# Projeto_PD_2021-02-18_15-49-25.net
KiCad netlist of a schematic drawn in EasyEDA
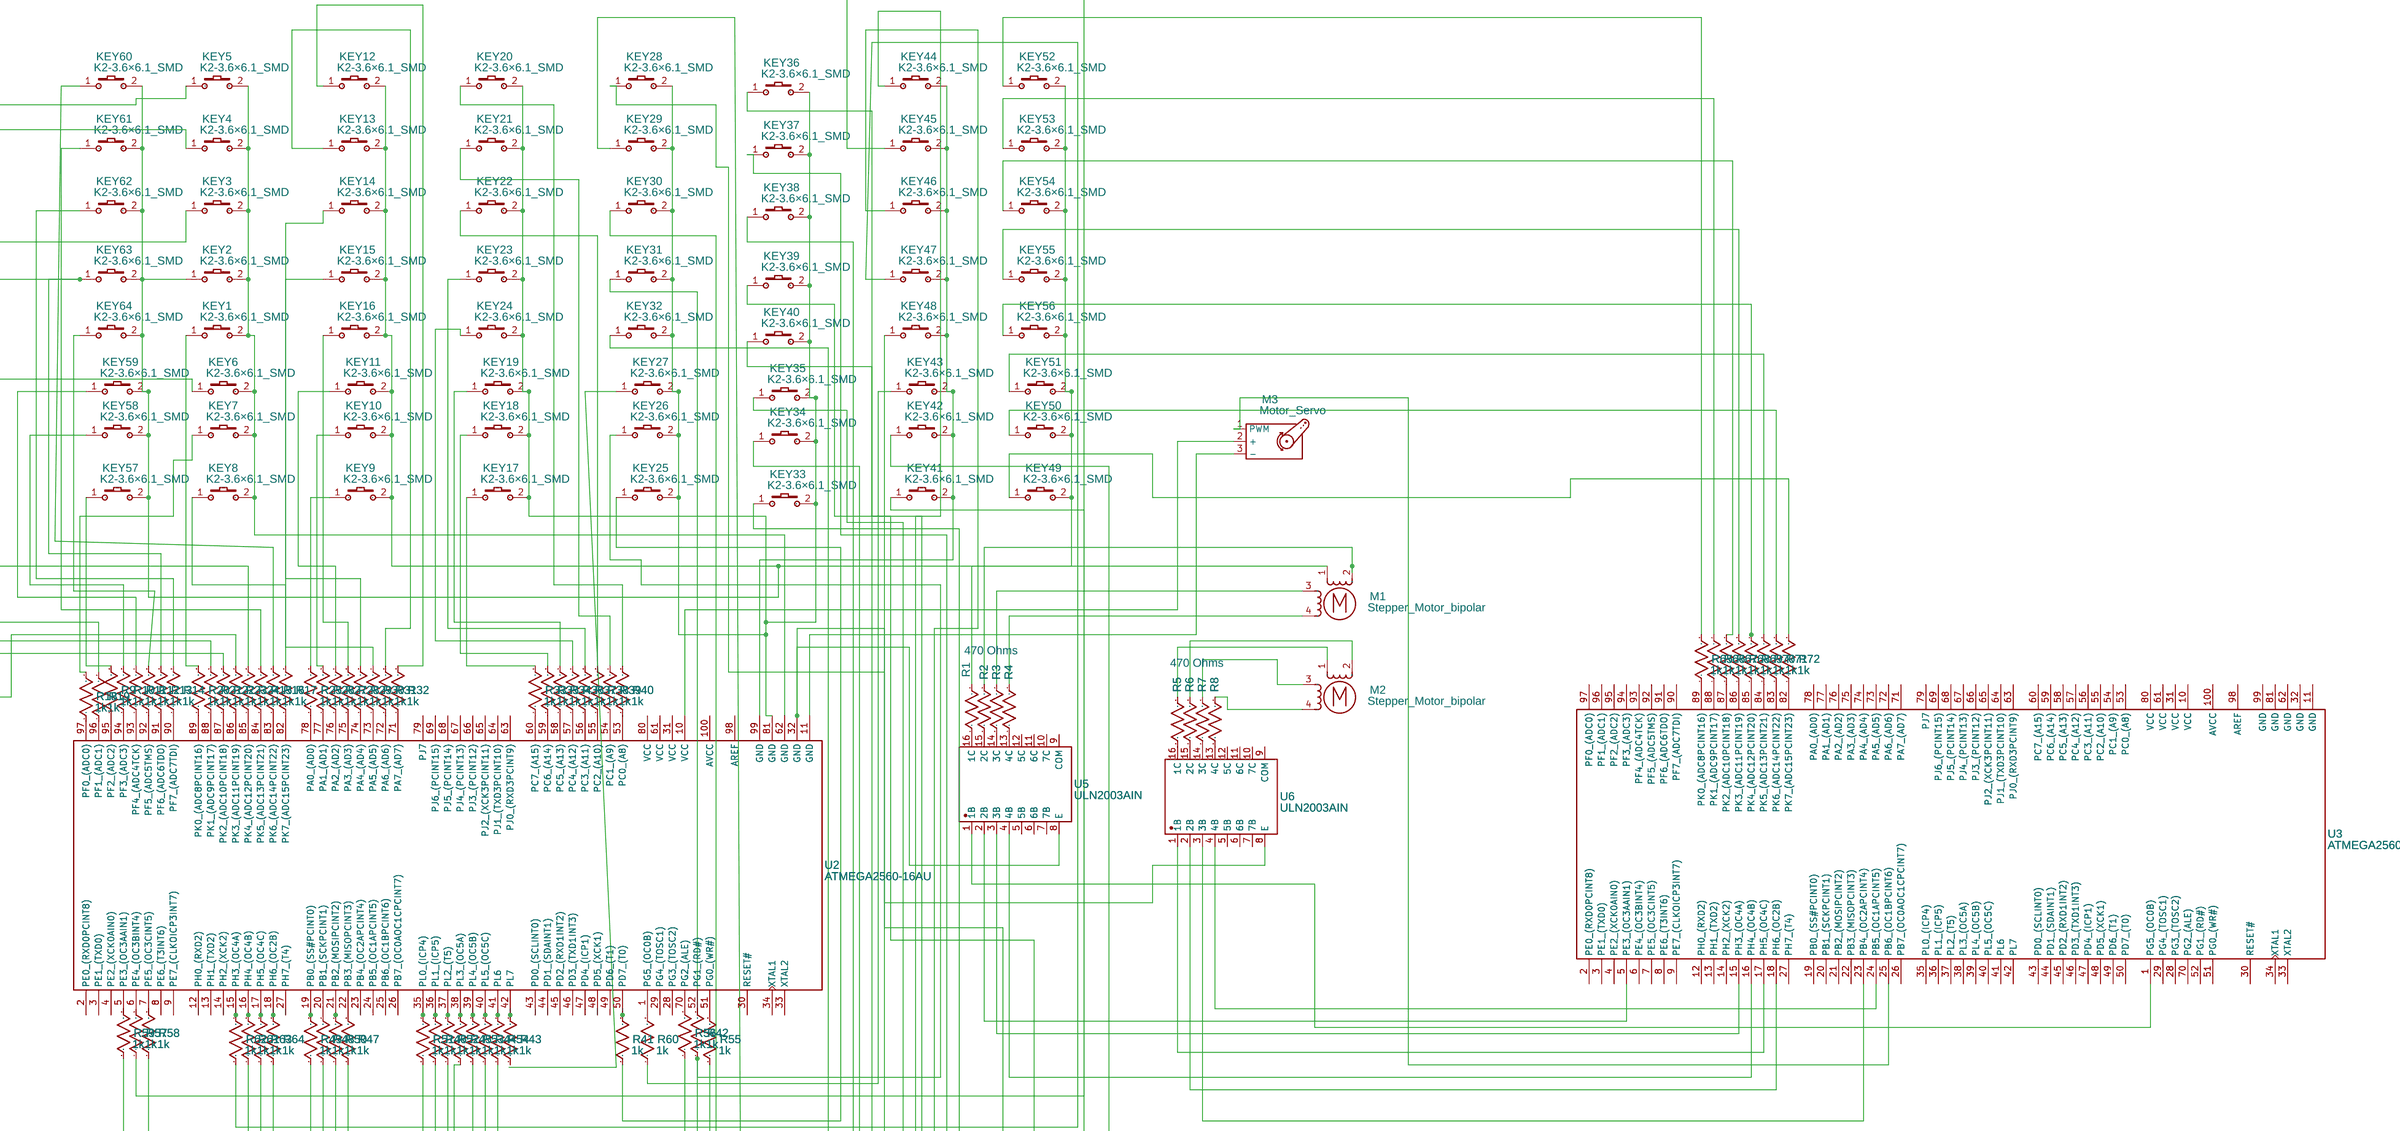
[diagram p0: schematic sheet]

(export (version "E")
  (design (tool "Eeschema 10.0.6"))
  (components
    (comp (ref "KEY1")
      (value "K2-3.6×6.1_SMD")
      (fields
        (field (name "BOM_Manufacturer Part") "K2-1107ST-A4SW-06")
        (field (name "BOM_Supplier Part") "C118141")
      )
      (libsource (lib "") (part "K2-3.6×6.1_SMD"))
    )
    (comp (ref "KEY2")
      (value "K2-3.6×6.1_SMD")
      (fields
        (field (name "BOM_Manufacturer Part") "K2-1107ST-A4SW-06")
        (field (name "BOM_Supplier Part") "C118141")
      )
      (libsource (lib "") (part "K2-3.6×6.1_SMD"))
    )
    (comp (ref "KEY3")
      (value "K2-3.6×6.1_SMD")
      (fields
        (field (name "BOM_Manufacturer Part") "K2-1107ST-A4SW-06")
        (field (name "BOM_Supplier Part") "C118141")
      )
      (libsource (lib "") (part "K2-3.6×6.1_SMD"))
    )
    (comp (ref "KEY4")
      (value "K2-3.6×6.1_SMD")
      (fields
        (field (name "BOM_Manufacturer Part") "K2-1107ST-A4SW-06")
        (field (name "BOM_Supplier Part") "C118141")
      )
      (libsource (lib "") (part "K2-3.6×6.1_SMD"))
    )
    (comp (ref "KEY5")
      (value "K2-3.6×6.1_SMD")
      (fields
        (field (name "BOM_Manufacturer Part") "K2-1107ST-A4SW-06")
        (field (name "BOM_Supplier Part") "C118141")
      )
      (libsource (lib "") (part "K2-3.6×6.1_SMD"))
    )
    (comp (ref "KEY6")
      (value "K2-3.6×6.1_SMD")
      (fields
        (field (name "BOM_Manufacturer Part") "K2-1107ST-A4SW-06")
        (field (name "BOM_Supplier Part") "C118141")
      )
      (libsource (lib "") (part "K2-3.6×6.1_SMD"))
    )
    (comp (ref "KEY7")
      (value "K2-3.6×6.1_SMD")
      (fields
        (field (name "BOM_Manufacturer Part") "K2-1107ST-A4SW-06")
        (field (name "BOM_Supplier Part") "C118141")
      )
      (libsource (lib "") (part "K2-3.6×6.1_SMD"))
    )
    (comp (ref "KEY8")
      (value "K2-3.6×6.1_SMD")
      (fields
        (field (name "BOM_Manufacturer Part") "K2-1107ST-A4SW-06")
        (field (name "BOM_Supplier Part") "C118141")
      )
      (libsource (lib "") (part "K2-3.6×6.1_SMD"))
    )
    (comp (ref "KEY9")
      (value "K2-3.6×6.1_SMD")
      (fields
        (field (name "BOM_Manufacturer Part") "K2-1107ST-A4SW-06")
        (field (name "BOM_Supplier Part") "C118141")
      )
      (libsource (lib "") (part "K2-3.6×6.1_SMD"))
    )
    (comp (ref "KEY10")
      (value "K2-3.6×6.1_SMD")
      (fields
        (field (name "BOM_Manufacturer Part") "K2-1107ST-A4SW-06")
        (field (name "BOM_Supplier Part") "C118141")
      )
      (libsource (lib "") (part "K2-3.6×6.1_SMD"))
    )
    (comp (ref "KEY11")
      (value "K2-3.6×6.1_SMD")
      (fields
        (field (name "BOM_Manufacturer Part") "K2-1107ST-A4SW-06")
        (field (name "BOM_Supplier Part") "C118141")
      )
      (libsource (lib "") (part "K2-3.6×6.1_SMD"))
    )
    (comp (ref "KEY12")
      (value "K2-3.6×6.1_SMD")
      (fields
        (field (name "BOM_Manufacturer Part") "K2-1107ST-A4SW-06")
        (field (name "BOM_Supplier Part") "C118141")
      )
      (libsource (lib "") (part "K2-3.6×6.1_SMD"))
    )
    (comp (ref "KEY13")
      (value "K2-3.6×6.1_SMD")
      (fields
        (field (name "BOM_Manufacturer Part") "K2-1107ST-A4SW-06")
        (field (name "BOM_Supplier Part") "C118141")
      )
      (libsource (lib "") (part "K2-3.6×6.1_SMD"))
    )
    (comp (ref "KEY14")
      (value "K2-3.6×6.1_SMD")
      (fields
        (field (name "BOM_Manufacturer Part") "K2-1107ST-A4SW-06")
        (field (name "BOM_Supplier Part") "C118141")
      )
      (libsource (lib "") (part "K2-3.6×6.1_SMD"))
    )
    (comp (ref "KEY15")
      (value "K2-3.6×6.1_SMD")
      (fields
        (field (name "BOM_Manufacturer Part") "K2-1107ST-A4SW-06")
        (field (name "BOM_Supplier Part") "C118141")
      )
      (libsource (lib "") (part "K2-3.6×6.1_SMD"))
    )
    (comp (ref "KEY16")
      (value "K2-3.6×6.1_SMD")
      (fields
        (field (name "BOM_Manufacturer Part") "K2-1107ST-A4SW-06")
        (field (name "BOM_Supplier Part") "C118141")
      )
      (libsource (lib "") (part "K2-3.6×6.1_SMD"))
    )
    (comp (ref "KEY17")
      (value "K2-3.6×6.1_SMD")
      (fields
        (field (name "BOM_Manufacturer Part") "K2-1107ST-A4SW-06")
        (field (name "BOM_Supplier Part") "C118141")
      )
      (libsource (lib "") (part "K2-3.6×6.1_SMD"))
    )
    (comp (ref "KEY18")
      (value "K2-3.6×6.1_SMD")
      (fields
        (field (name "BOM_Manufacturer Part") "K2-1107ST-A4SW-06")
        (field (name "BOM_Supplier Part") "C118141")
      )
      (libsource (lib "") (part "K2-3.6×6.1_SMD"))
    )
    (comp (ref "KEY19")
      (value "K2-3.6×6.1_SMD")
      (fields
        (field (name "BOM_Manufacturer Part") "K2-1107ST-A4SW-06")
        (field (name "BOM_Supplier Part") "C118141")
      )
      (libsource (lib "") (part "K2-3.6×6.1_SMD"))
    )
    (comp (ref "KEY20")
      (value "K2-3.6×6.1_SMD")
      (fields
        (field (name "BOM_Manufacturer Part") "K2-1107ST-A4SW-06")
        (field (name "BOM_Supplier Part") "C118141")
      )
      (libsource (lib "") (part "K2-3.6×6.1_SMD"))
    )
    (comp (ref "KEY21")
      (value "K2-3.6×6.1_SMD")
      (fields
        (field (name "BOM_Manufacturer Part") "K2-1107ST-A4SW-06")
        (field (name "BOM_Supplier Part") "C118141")
      )
      (libsource (lib "") (part "K2-3.6×6.1_SMD"))
    )
    (comp (ref "KEY22")
      (value "K2-3.6×6.1_SMD")
      (fields
        (field (name "BOM_Manufacturer Part") "K2-1107ST-A4SW-06")
        (field (name "BOM_Supplier Part") "C118141")
      )
      (libsource (lib "") (part "K2-3.6×6.1_SMD"))
    )
    (comp (ref "KEY23")
      (value "K2-3.6×6.1_SMD")
      (fields
        (field (name "BOM_Manufacturer Part") "K2-1107ST-A4SW-06")
        (field (name "BOM_Supplier Part") "C118141")
      )
      (libsource (lib "") (part "K2-3.6×6.1_SMD"))
    )
    (comp (ref "KEY24")
      (value "K2-3.6×6.1_SMD")
      (fields
        (field (name "BOM_Manufacturer Part") "K2-1107ST-A4SW-06")
        (field (name "BOM_Supplier Part") "C118141")
      )
      (libsource (lib "") (part "K2-3.6×6.1_SMD"))
    )
    (comp (ref "KEY25")
      (value "K2-3.6×6.1_SMD")
      (fields
        (field (name "BOM_Manufacturer Part") "K2-1107ST-A4SW-06")
        (field (name "BOM_Supplier Part") "C118141")
      )
      (libsource (lib "") (part "K2-3.6×6.1_SMD"))
    )
    (comp (ref "KEY26")
      (value "K2-3.6×6.1_SMD")
      (fields
        (field (name "BOM_Manufacturer Part") "K2-1107ST-A4SW-06")
        (field (name "BOM_Supplier Part") "C118141")
      )
      (libsource (lib "") (part "K2-3.6×6.1_SMD"))
    )
    (comp (ref "KEY27")
      (value "K2-3.6×6.1_SMD")
      (fields
        (field (name "BOM_Manufacturer Part") "K2-1107ST-A4SW-06")
        (field (name "BOM_Supplier Part") "C118141")
      )
      (libsource (lib "") (part "K2-3.6×6.1_SMD"))
    )
    (comp (ref "KEY28")
      (value "K2-3.6×6.1_SMD")
      (fields
        (field (name "BOM_Manufacturer Part") "K2-1107ST-A4SW-06")
        (field (name "BOM_Supplier Part") "C118141")
      )
      (libsource (lib "") (part "K2-3.6×6.1_SMD"))
    )
    (comp (ref "KEY29")
      (value "K2-3.6×6.1_SMD")
      (fields
        (field (name "BOM_Manufacturer Part") "K2-1107ST-A4SW-06")
        (field (name "BOM_Supplier Part") "C118141")
      )
      (libsource (lib "") (part "K2-3.6×6.1_SMD"))
    )
    (comp (ref "KEY30")
      (value "K2-3.6×6.1_SMD")
      (fields
        (field (name "BOM_Manufacturer Part") "K2-1107ST-A4SW-06")
        (field (name "BOM_Supplier Part") "C118141")
      )
      (libsource (lib "") (part "K2-3.6×6.1_SMD"))
    )
    (comp (ref "KEY31")
      (value "K2-3.6×6.1_SMD")
      (fields
        (field (name "BOM_Manufacturer Part") "K2-1107ST-A4SW-06")
        (field (name "BOM_Supplier Part") "C118141")
      )
      (libsource (lib "") (part "K2-3.6×6.1_SMD"))
    )
    (comp (ref "KEY32")
      (value "K2-3.6×6.1_SMD")
      (fields
        (field (name "BOM_Manufacturer Part") "K2-1107ST-A4SW-06")
        (field (name "BOM_Supplier Part") "C118141")
      )
      (libsource (lib "") (part "K2-3.6×6.1_SMD"))
    )
    (comp (ref "KEY33")
      (value "K2-3.6×6.1_SMD")
      (fields
        (field (name "BOM_Manufacturer Part") "K2-1107ST-A4SW-06")
        (field (name "BOM_Supplier Part") "C118141")
      )
      (libsource (lib "") (part "K2-3.6×6.1_SMD"))
    )
    (comp (ref "KEY34")
      (value "K2-3.6×6.1_SMD")
      (fields
        (field (name "BOM_Manufacturer Part") "K2-1107ST-A4SW-06")
        (field (name "BOM_Supplier Part") "C118141")
      )
      (libsource (lib "") (part "K2-3.6×6.1_SMD"))
    )
    (comp (ref "KEY35")
      (value "K2-3.6×6.1_SMD")
      (fields
        (field (name "BOM_Manufacturer Part") "K2-1107ST-A4SW-06")
        (field (name "BOM_Supplier Part") "C118141")
      )
      (libsource (lib "") (part "K2-3.6×6.1_SMD"))
    )
    (comp (ref "KEY36")
      (value "K2-3.6×6.1_SMD")
      (fields
        (field (name "BOM_Manufacturer Part") "K2-1107ST-A4SW-06")
        (field (name "BOM_Supplier Part") "C118141")
      )
      (libsource (lib "") (part "K2-3.6×6.1_SMD"))
    )
    (comp (ref "KEY37")
      (value "K2-3.6×6.1_SMD")
      (fields
        (field (name "BOM_Manufacturer Part") "K2-1107ST-A4SW-06")
        (field (name "BOM_Supplier Part") "C118141")
      )
      (libsource (lib "") (part "K2-3.6×6.1_SMD"))
    )
    (comp (ref "KEY38")
      (value "K2-3.6×6.1_SMD")
      (fields
        (field (name "BOM_Manufacturer Part") "K2-1107ST-A4SW-06")
        (field (name "BOM_Supplier Part") "C118141")
      )
      (libsource (lib "") (part "K2-3.6×6.1_SMD"))
    )
    (comp (ref "KEY39")
      (value "K2-3.6×6.1_SMD")
      (fields
        (field (name "BOM_Manufacturer Part") "K2-1107ST-A4SW-06")
        (field (name "BOM_Supplier Part") "C118141")
      )
      (libsource (lib "") (part "K2-3.6×6.1_SMD"))
    )
    (comp (ref "KEY40")
      (value "K2-3.6×6.1_SMD")
      (fields
        (field (name "BOM_Manufacturer Part") "K2-1107ST-A4SW-06")
        (field (name "BOM_Supplier Part") "C118141")
      )
      (libsource (lib "") (part "K2-3.6×6.1_SMD"))
    )
    (comp (ref "KEY41")
      (value "K2-3.6×6.1_SMD")
      (fields
        (field (name "BOM_Manufacturer Part") "K2-1107ST-A4SW-06")
        (field (name "BOM_Supplier Part") "C118141")
      )
      (libsource (lib "") (part "K2-3.6×6.1_SMD"))
    )
    (comp (ref "KEY42")
      (value "K2-3.6×6.1_SMD")
      (fields
        (field (name "BOM_Manufacturer Part") "K2-1107ST-A4SW-06")
        (field (name "BOM_Supplier Part") "C118141")
      )
      (libsource (lib "") (part "K2-3.6×6.1_SMD"))
    )
    (comp (ref "KEY43")
      (value "K2-3.6×6.1_SMD")
      (fields
        (field (name "BOM_Manufacturer Part") "K2-1107ST-A4SW-06")
        (field (name "BOM_Supplier Part") "C118141")
      )
      (libsource (lib "") (part "K2-3.6×6.1_SMD"))
    )
    (comp (ref "KEY44")
      (value "K2-3.6×6.1_SMD")
      (fields
        (field (name "BOM_Manufacturer Part") "K2-1107ST-A4SW-06")
        (field (name "BOM_Supplier Part") "C118141")
      )
      (libsource (lib "") (part "K2-3.6×6.1_SMD"))
    )
    (comp (ref "KEY45")
      (value "K2-3.6×6.1_SMD")
      (fields
        (field (name "BOM_Manufacturer Part") "K2-1107ST-A4SW-06")
        (field (name "BOM_Supplier Part") "C118141")
      )
      (libsource (lib "") (part "K2-3.6×6.1_SMD"))
    )
    (comp (ref "KEY46")
      (value "K2-3.6×6.1_SMD")
      (fields
        (field (name "BOM_Manufacturer Part") "K2-1107ST-A4SW-06")
        (field (name "BOM_Supplier Part") "C118141")
      )
      (libsource (lib "") (part "K2-3.6×6.1_SMD"))
    )
    (comp (ref "KEY47")
      (value "K2-3.6×6.1_SMD")
      (fields
        (field (name "BOM_Manufacturer Part") "K2-1107ST-A4SW-06")
        (field (name "BOM_Supplier Part") "C118141")
      )
      (libsource (lib "") (part "K2-3.6×6.1_SMD"))
    )
    (comp (ref "KEY48")
      (value "K2-3.6×6.1_SMD")
      (fields
        (field (name "BOM_Manufacturer Part") "K2-1107ST-A4SW-06")
        (field (name "BOM_Supplier Part") "C118141")
      )
      (libsource (lib "") (part "K2-3.6×6.1_SMD"))
    )
    (comp (ref "KEY49")
      (value "K2-3.6×6.1_SMD")
      (fields
        (field (name "BOM_Manufacturer Part") "K2-1107ST-A4SW-06")
        (field (name "BOM_Supplier Part") "C118141")
      )
      (libsource (lib "") (part "K2-3.6×6.1_SMD"))
    )
    (comp (ref "KEY50")
      (value "K2-3.6×6.1_SMD")
      (fields
        (field (name "BOM_Manufacturer Part") "K2-1107ST-A4SW-06")
        (field (name "BOM_Supplier Part") "C118141")
      )
      (libsource (lib "") (part "K2-3.6×6.1_SMD"))
    )
    (comp (ref "KEY51")
      (value "K2-3.6×6.1_SMD")
      (fields
        (field (name "BOM_Manufacturer Part") "K2-1107ST-A4SW-06")
        (field (name "BOM_Supplier Part") "C118141")
      )
      (libsource (lib "") (part "K2-3.6×6.1_SMD"))
    )
    (comp (ref "KEY52")
      (value "K2-3.6×6.1_SMD")
      (fields
        (field (name "BOM_Manufacturer Part") "K2-1107ST-A4SW-06")
        (field (name "BOM_Supplier Part") "C118141")
      )
      (libsource (lib "") (part "K2-3.6×6.1_SMD"))
    )
    (comp (ref "KEY53")
      (value "K2-3.6×6.1_SMD")
      (fields
        (field (name "BOM_Manufacturer Part") "K2-1107ST-A4SW-06")
        (field (name "BOM_Supplier Part") "C118141")
      )
      (libsource (lib "") (part "K2-3.6×6.1_SMD"))
    )
    (comp (ref "KEY54")
      (value "K2-3.6×6.1_SMD")
      (fields
        (field (name "BOM_Manufacturer Part") "K2-1107ST-A4SW-06")
        (field (name "BOM_Supplier Part") "C118141")
      )
      (libsource (lib "") (part "K2-3.6×6.1_SMD"))
    )
    (comp (ref "KEY55")
      (value "K2-3.6×6.1_SMD")
      (fields
        (field (name "BOM_Manufacturer Part") "K2-1107ST-A4SW-06")
        (field (name "BOM_Supplier Part") "C118141")
      )
      (libsource (lib "") (part "K2-3.6×6.1_SMD"))
    )
    (comp (ref "KEY56")
      (value "K2-3.6×6.1_SMD")
      (fields
        (field (name "BOM_Manufacturer Part") "K2-1107ST-A4SW-06")
        (field (name "BOM_Supplier Part") "C118141")
      )
      (libsource (lib "") (part "K2-3.6×6.1_SMD"))
    )
    (comp (ref "KEY57")
      (value "K2-3.6×6.1_SMD")
      (fields
        (field (name "BOM_Manufacturer Part") "K2-1107ST-A4SW-06")
        (field (name "BOM_Supplier Part") "C118141")
      )
      (libsource (lib "") (part "K2-3.6×6.1_SMD"))
    )
    (comp (ref "KEY58")
      (value "K2-3.6×6.1_SMD")
      (fields
        (field (name "BOM_Manufacturer Part") "K2-1107ST-A4SW-06")
        (field (name "BOM_Supplier Part") "C118141")
      )
      (libsource (lib "") (part "K2-3.6×6.1_SMD"))
    )
    (comp (ref "KEY59")
      (value "K2-3.6×6.1_SMD")
      (fields
        (field (name "BOM_Manufacturer Part") "K2-1107ST-A4SW-06")
        (field (name "BOM_Supplier Part") "C118141")
      )
      (libsource (lib "") (part "K2-3.6×6.1_SMD"))
    )
    (comp (ref "KEY60")
      (value "K2-3.6×6.1_SMD")
      (fields
        (field (name "BOM_Manufacturer Part") "K2-1107ST-A4SW-06")
        (field (name "BOM_Supplier Part") "C118141")
      )
      (libsource (lib "") (part "K2-3.6×6.1_SMD"))
    )
    (comp (ref "KEY61")
      (value "K2-3.6×6.1_SMD")
      (fields
        (field (name "BOM_Manufacturer Part") "K2-1107ST-A4SW-06")
        (field (name "BOM_Supplier Part") "C118141")
      )
      (libsource (lib "") (part "K2-3.6×6.1_SMD"))
    )
    (comp (ref "KEY62")
      (value "K2-3.6×6.1_SMD")
      (fields
        (field (name "BOM_Manufacturer Part") "K2-1107ST-A4SW-06")
        (field (name "BOM_Supplier Part") "C118141")
      )
      (libsource (lib "") (part "K2-3.6×6.1_SMD"))
    )
    (comp (ref "KEY63")
      (value "K2-3.6×6.1_SMD")
      (fields
        (field (name "BOM_Manufacturer Part") "K2-1107ST-A4SW-06")
        (field (name "BOM_Supplier Part") "C118141")
      )
      (libsource (lib "") (part "K2-3.6×6.1_SMD"))
    )
    (comp (ref "KEY64")
      (value "K2-3.6×6.1_SMD")
      (fields
        (field (name "BOM_Manufacturer Part") "K2-1107ST-A4SW-06")
        (field (name "BOM_Supplier Part") "C118141")
      )
      (libsource (lib "") (part "K2-3.6×6.1_SMD"))
    )
    (comp (ref "M1") (value "Stepper_Motor_bipolar") (libsource (lib "") (part "Stepper_Motor_bipolar")))
    (comp (ref "M2") (value "Stepper_Motor_bipolar") (libsource (lib "") (part "Stepper_Motor_bipolar")))
    (comp (ref "M3") (value "Motor_Servo") (libsource (lib "") (part "Motor_Servo")))
    (comp (ref "R1") (value "1k") (libsource (lib "") (part "R_0603_US")))
    (comp (ref "R2") (value "1k") (libsource (lib "") (part "R_0603_US")))
    (comp (ref "R3") (value "470") (libsource (lib "") (part "R_0603_US")))
    (comp (ref "R4") (value "470") (libsource (lib "") (part "R_0603_US")))
    (comp (ref "R5") (value "470") (libsource (lib "") (part "R_0603_US")))
    (comp (ref "R6") (value "470") (libsource (lib "") (part "R_0603_US")))
    (comp (ref "R7") (value "470") (libsource (lib "") (part "R_0603_US")))
    (comp (ref "R8") (value "470") (libsource (lib "") (part "R_0603_US")))
    (comp (ref "R9") (value "1k") (libsource (lib "") (part "R_0603_US")))
    (comp (ref "R10") (value "1k") (libsource (lib "") (part "R_0603_US")))
    (comp (ref "R11") (value "1k") (libsource (lib "") (part "R_0603_US")))
    (comp (ref "R12") (value "1k") (libsource (lib "") (part "R_0603_US")))
    (comp (ref "R13") (value "1k") (libsource (lib "") (part "R_0603_US")))
    (comp (ref "R14") (value "1k") (libsource (lib "") (part "R_0603_US")))
    (comp (ref "R15") (value "1k") (libsource (lib "") (part "R_0603_US")))
    (comp (ref "R16") (value "1k") (libsource (lib "") (part "R_0603_US")))
    (comp (ref "R17") (value "1k") (libsource (lib "") (part "R_0603_US")))
    (comp (ref "R18") (value "1k") (libsource (lib "") (part "R_0603_US")))
    (comp (ref "R19") (value "1k") (libsource (lib "") (part "R_0603_US")))
    (comp (ref "R20") (value "1k") (libsource (lib "") (part "R_0603_US")))
    (comp (ref "R21") (value "1k") (libsource (lib "") (part "R_0603_US")))
    (comp (ref "R22") (value "1k") (libsource (lib "") (part "R_0603_US")))
    (comp (ref "R23") (value "1k") (libsource (lib "") (part "R_0603_US")))
    (comp (ref "R24") (value "1k") (libsource (lib "") (part "R_0603_US")))
    (comp (ref "R25") (value "1k") (libsource (lib "") (part "R_0603_US")))
    (comp (ref "R26") (value "1k") (libsource (lib "") (part "R_0603_US")))
    (comp (ref "R27") (value "1k") (libsource (lib "") (part "R_0603_US")))
    (comp (ref "R28") (value "1k") (libsource (lib "") (part "R_0603_US")))
    (comp (ref "R29") (value "1k") (libsource (lib "") (part "R_0603_US")))
    (comp (ref "R30") (value "1k") (libsource (lib "") (part "R_0603_US")))
    (comp (ref "R31") (value "1k") (libsource (lib "") (part "R_0603_US")))
    (comp (ref "R32") (value "1k") (libsource (lib "") (part "R_0603_US")))
    (comp (ref "R33") (value "1k") (libsource (lib "") (part "R_0603_US")))
    (comp (ref "R34") (value "1k") (libsource (lib "") (part "R_0603_US")))
    (comp (ref "R35") (value "1k") (libsource (lib "") (part "R_0603_US")))
    (comp (ref "R36") (value "1k") (libsource (lib "") (part "R_0603_US")))
    (comp (ref "R37") (value "1k") (libsource (lib "") (part "R_0603_US")))
    (comp (ref "R38") (value "1k") (libsource (lib "") (part "R_0603_US")))
    (comp (ref "R39") (value "1k") (libsource (lib "") (part "R_0603_US")))
    (comp (ref "R40") (value "1k") (libsource (lib "") (part "R_0603_US")))
    (comp (ref "R41") (value "1k") (libsource (lib "") (part "R_0603_US")))
    (comp (ref "R42") (value "1k") (libsource (lib "") (part "R_0603_US")))
    (comp (ref "R43") (value "1k") (libsource (lib "") (part "R_0603_US")))
    (comp (ref "R44") (value "1k") (libsource (lib "") (part "R_0603_US")))
    (comp (ref "R45") (value "1k") (libsource (lib "") (part "R_0603_US")))
    (comp (ref "R46") (value "1k") (libsource (lib "") (part "R_0603_US")))
    (comp (ref "R47") (value "1k") (libsource (lib "") (part "R_0603_US")))
    (comp (ref "R48") (value "1k") (libsource (lib "") (part "R_0603_US")))
    (comp (ref "R49") (value "1k") (libsource (lib "") (part "R_0603_US")))
    (comp (ref "R50") (value "1k") (libsource (lib "") (part "R_0603_US")))
    (comp (ref "R51") (value "1k") (libsource (lib "") (part "R_0603_US")))
    (comp (ref "R52") (value "1k") (libsource (lib "") (part "R_0603_US")))
    (comp (ref "R53") (value "1k") (libsource (lib "") (part "R_0603_US")))
    (comp (ref "R54") (value "1k") (libsource (lib "") (part "R_0603_US")))
    (comp (ref "R55") (value "1k") (libsource (lib "") (part "R_0603_US")))
    (comp (ref "R56") (value "1k") (libsource (lib "") (part "R_0603_US")))
    (comp (ref "R57") (value "1k") (libsource (lib "") (part "R_0603_US")))
    (comp (ref "R58") (value "1k") (libsource (lib "") (part "R_0603_US")))
    (comp (ref "R59") (value "1k") (libsource (lib "") (part "R_0603_US")))
    (comp (ref "R60") (value "1k") (libsource (lib "") (part "R_0603_US")))
    (comp (ref "R61") (value "1k") (libsource (lib "") (part "R_0603_US")))
    (comp (ref "R62") (value "1k") (libsource (lib "") (part "R_0603_US")))
    (comp (ref "R63") (value "1k") (libsource (lib "") (part "R_0603_US")))
    (comp (ref "R64") (value "1k") (libsource (lib "") (part "R_0603_US")))
    (comp (ref "R65") (value "1k") (libsource (lib "") (part "R_0603_US")))
    (comp (ref "R66") (value "1k") (libsource (lib "") (part "R_0603_US")))
    (comp (ref "R67") (value "1k") (libsource (lib "") (part "R_0603_US")))
    (comp (ref "R68") (value "1k") (libsource (lib "") (part "R_0603_US")))
    (comp (ref "R69") (value "1k") (libsource (lib "") (part "R_0603_US")))
    (comp (ref "R70") (value "1k") (libsource (lib "") (part "R_0603_US")))
    (comp (ref "R71") (value "1k") (libsource (lib "") (part "R_0603_US")))
    (comp (ref "R72") (value "1k") (libsource (lib "") (part "R_0603_US")))
    (comp (ref "U2")
      (value "ATMEGA2560-16AU")
      (fields (field (name "BOM_Supplier Part") "C22460"))
      (libsource (lib "") (part "ATMEGA2560-16AU"))
    )
    (comp (ref "U3")
      (value "ATMEGA2560-16AU")
      (fields (field (name "BOM_Supplier Part") "C22460"))
      (libsource (lib "") (part "ATMEGA2560-16AU"))
    )
    (comp (ref "U5")
      (value "ULN2003AIN")
      (fields (field (name "BOM_Supplier Part") "C90838"))
      (libsource (lib "") (part "ULN2003AIN"))
    )
    (comp (ref "U6")
      (value "ULN2003AIN")
      (fields (field (name "BOM_Supplier Part") "C90838"))
      (libsource (lib "") (part "ULN2003AIN"))
    )
  )
  (nets
    (net (code "1") (name "Net-(KEY1-Pad1)") (class "Default")
      (node (ref "KEY1") (pin "1") (pinfunction "1_1") (pintype "unspecified"))
      (node (ref "R20") (pin "2") (pinfunction "2_2") (pintype "unspecified"))
    )
    (net (code "2") (name "Net-(KEY1-Pad2)") (class "Default")
      (node (ref "KEY1") (pin "2") (pinfunction "2_2") (pintype "unspecified"))
      (node (ref "KEY2") (pin "2") (pinfunction "2_2") (pintype "unspecified"))
      (node (ref "KEY3") (pin "2") (pinfunction "2_2") (pintype "unspecified"))
      (node (ref "KEY4") (pin "2") (pinfunction "2_2") (pintype "unspecified"))
      (node (ref "KEY5") (pin "2") (pinfunction "2_2") (pintype "unspecified"))
      (node (ref "KEY6") (pin "2") (pinfunction "2_2") (pintype "unspecified"))
      (node (ref "KEY7") (pin "2") (pinfunction "2_2") (pintype "unspecified"))
      (node (ref "KEY8") (pin "2") (pinfunction "2_2") (pintype "unspecified"))
      (node (ref "U2") (pin "62") (pinfunction "GND_62") (pintype "passive"))
    )
    (net (code "3") (name "Net-(KEY3-Pad1)") (class "Default")
      (node (ref "KEY3") (pin "1") (pinfunction "1_1") (pintype "unspecified"))
      (node (ref "R22") (pin "2") (pinfunction "2_2") (pintype "unspecified"))
    )
    (net (code "4") (name "Net-(KEY4-Pad1)") (class "Default")
      (node (ref "KEY4") (pin "1") (pinfunction "1_1") (pintype "unspecified"))
      (node (ref "R23") (pin "2") (pinfunction "2_2") (pintype "unspecified"))
    )
    (net (code "5") (name "Net-(KEY5-Pad1)") (class "Default")
      (node (ref "KEY5") (pin "1") (pinfunction "1_1") (pintype "unspecified"))
      (node (ref "R24") (pin "2") (pinfunction "2_2") (pintype "unspecified"))
    )
    (net (code "6") (name "Net-(KEY6-Pad1)") (class "Default")
      (node (ref "KEY6") (pin "1") (pinfunction "1_1") (pintype "unspecified"))
      (node (ref "R19") (pin "2") (pinfunction "2_2") (pintype "unspecified"))
    )
    (net (code "7") (name "Net-(KEY7-Pad1)") (class "Default")
      (node (ref "KEY7") (pin "1") (pinfunction "1_1") (pintype "unspecified"))
      (node (ref "R18") (pin "2") (pinfunction "2_2") (pintype "unspecified"))
    )
    (net (code "8") (name "Net-(KEY8-Pad1)") (class "Default")
      (node (ref "KEY8") (pin "1") (pinfunction "1_1") (pintype "unspecified"))
      (node (ref "R17") (pin "2") (pinfunction "2_2") (pintype "unspecified"))
    )
    (net (code "9") (name "Net-(KEY9-Pad1)") (class "Default")
      (node (ref "KEY9") (pin "1") (pinfunction "1_1") (pintype "unspecified"))
      (node (ref "R25") (pin "2") (pinfunction "2_2") (pintype "unspecified"))
    )
    (net (code "10") (name "Net-(KEY10-Pad1)") (class "Default")
      (node (ref "KEY10") (pin "1") (pinfunction "1_1") (pintype "unspecified"))
      (node (ref "R26") (pin "2") (pinfunction "2_2") (pintype "unspecified"))
    )
    (net (code "11") (name "Net-(KEY10-Pad2)") (class "Default")
      (node (ref "KEY10") (pin "2") (pinfunction "2_2") (pintype "unspecified"))
      (node (ref "KEY11") (pin "2") (pinfunction "2_2") (pintype "unspecified"))
      (node (ref "KEY12") (pin "2") (pinfunction "2_2") (pintype "unspecified"))
      (node (ref "KEY13") (pin "2") (pinfunction "2_2") (pintype "unspecified"))
      (node (ref "KEY14") (pin "2") (pinfunction "2_2") (pintype "unspecified"))
      (node (ref "KEY15") (pin "2") (pinfunction "2_2") (pintype "unspecified"))
      (node (ref "KEY16") (pin "2") (pinfunction "2_2") (pintype "unspecified"))
      (node (ref "KEY2") (pin "1") (pinfunction "1_1") (pintype "unspecified"))
      (node (ref "KEY49") (pin "2") (pinfunction "2_2") (pintype "unspecified"))
      (node (ref "KEY50") (pin "2") (pinfunction "2_2") (pintype "unspecified"))
      (node (ref "KEY51") (pin "2") (pinfunction "2_2") (pintype "unspecified"))
      (node (ref "KEY52") (pin "2") (pinfunction "2_2") (pintype "unspecified"))
      (node (ref "KEY53") (pin "2") (pinfunction "2_2") (pintype "unspecified"))
      (node (ref "KEY54") (pin "2") (pinfunction "2_2") (pintype "unspecified"))
      (node (ref "KEY55") (pin "2") (pinfunction "2_2") (pintype "unspecified"))
      (node (ref "KEY56") (pin "2") (pinfunction "2_2") (pintype "unspecified"))
      (node (ref "KEY57") (pin "2") (pinfunction "2_2") (pintype "unspecified"))
      (node (ref "KEY58") (pin "2") (pinfunction "2_2") (pintype "unspecified"))
      (node (ref "KEY59") (pin "2") (pinfunction "2_2") (pintype "unspecified"))
      (node (ref "KEY60") (pin "2") (pinfunction "2_2") (pintype "unspecified"))
      (node (ref "KEY61") (pin "2") (pinfunction "2_2") (pintype "unspecified"))
      (node (ref "KEY62") (pin "2") (pinfunction "2_2") (pintype "unspecified"))
      (node (ref "KEY63") (pin "2") (pinfunction "2_2") (pintype "unspecified"))
      (node (ref "KEY64") (pin "2") (pinfunction "2_2") (pintype "unspecified"))
      (node (ref "KEY9") (pin "2") (pinfunction "2_2") (pintype "unspecified"))
    )
    (net (code "12") (name "Net-(KEY11-Pad1)") (class "Default")
      (node (ref "KEY11") (pin "1") (pinfunction "1_1") (pintype "unspecified"))
      (node (ref "R27") (pin "2") (pinfunction "2_2") (pintype "unspecified"))
    )
    (net (code "13") (name "Net-(KEY12-Pad1)") (class "Default")
      (node (ref "KEY12") (pin "1") (pinfunction "1_1") (pintype "unspecified"))
      (node (ref "R32") (pin "2") (pinfunction "2_2") (pintype "unspecified"))
    )
    (net (code "14") (name "Net-(KEY13-Pad1)") (class "Default")
      (node (ref "KEY13") (pin "1") (pinfunction "1_1") (pintype "unspecified"))
      (node (ref "R31") (pin "2") (pinfunction "2_2") (pintype "unspecified"))
    )
    (net (code "15") (name "Net-(KEY14-Pad1)") (class "Default")
      (node (ref "KEY14") (pin "1") (pinfunction "1_1") (pintype "unspecified"))
      (node (ref "R30") (pin "2") (pinfunction "2_2") (pintype "unspecified"))
    )
    (net (code "16") (name "Net-(KEY15-Pad1)") (class "Default")
      (node (ref "KEY15") (pin "1") (pinfunction "1_1") (pintype "unspecified"))
      (node (ref "R29") (pin "2") (pinfunction "2_2") (pintype "unspecified"))
    )
    (net (code "17") (name "Net-(KEY16-Pad1)") (class "Default")
      (node (ref "KEY16") (pin "1") (pinfunction "1_1") (pintype "unspecified"))
      (node (ref "R28") (pin "2") (pinfunction "2_2") (pintype "unspecified"))
    )
    (net (code "18") (name "Net-(KEY17-Pad1)") (class "Default")
      (node (ref "KEY17") (pin "1") (pinfunction "1_1") (pintype "unspecified"))
      (node (ref "R33") (pin "2") (pinfunction "2_2") (pintype "unspecified"))
    )
    (net (code "19") (name "Net-(KEY17-Pad2)") (class "Default")
      (node (ref "KEY17") (pin "2") (pinfunction "2_2") (pintype "unspecified"))
      (node (ref "KEY18") (pin "2") (pinfunction "2_2") (pintype "unspecified"))
      (node (ref "KEY19") (pin "2") (pinfunction "2_2") (pintype "unspecified"))
      (node (ref "KEY20") (pin "2") (pinfunction "2_2") (pintype "unspecified"))
      (node (ref "KEY21") (pin "2") (pinfunction "2_2") (pintype "unspecified"))
      (node (ref "KEY22") (pin "2") (pinfunction "2_2") (pintype "unspecified"))
      (node (ref "KEY23") (pin "2") (pinfunction "2_2") (pintype "unspecified"))
      (node (ref "KEY24") (pin "2") (pinfunction "2_2") (pintype "unspecified"))
      (node (ref "KEY25") (pin "2") (pinfunction "2_2") (pintype "unspecified"))
      (node (ref "KEY26") (pin "2") (pinfunction "2_2") (pintype "unspecified"))
      (node (ref "KEY27") (pin "2") (pinfunction "2_2") (pintype "unspecified"))
      (node (ref "KEY28") (pin "2") (pinfunction "2_2") (pintype "unspecified"))
      (node (ref "KEY29") (pin "2") (pinfunction "2_2") (pintype "unspecified"))
      (node (ref "KEY30") (pin "2") (pinfunction "2_2") (pintype "unspecified"))
      (node (ref "KEY31") (pin "2") (pinfunction "2_2") (pintype "unspecified"))
      (node (ref "KEY32") (pin "2") (pinfunction "2_2") (pintype "unspecified"))
      (node (ref "KEY33") (pin "2") (pinfunction "2_2") (pintype "unspecified"))
      (node (ref "KEY34") (pin "2") (pinfunction "2_2") (pintype "unspecified"))
      (node (ref "KEY35") (pin "2") (pinfunction "2_2") (pintype "unspecified"))
      (node (ref "KEY36") (pin "2") (pinfunction "2_2") (pintype "unspecified"))
      (node (ref "KEY37") (pin "2") (pinfunction "2_2") (pintype "unspecified"))
      (node (ref "KEY38") (pin "2") (pinfunction "2_2") (pintype "unspecified"))
      (node (ref "KEY39") (pin "2") (pinfunction "2_2") (pintype "unspecified"))
      (node (ref "KEY40") (pin "2") (pinfunction "2_2") (pintype "unspecified"))
      (node (ref "U2") (pin "81") (pinfunction "GND_81") (pintype "passive"))
    )
    (net (code "20") (name "Net-(KEY18-Pad1)") (class "Default")
      (node (ref "KEY18") (pin "1") (pinfunction "1_1") (pintype "unspecified"))
      (node (ref "R35") (pin "2") (pinfunction "2_2") (pintype "unspecified"))
    )
    (net (code "21") (name "Net-(KEY19-Pad1)") (class "Default")
      (node (ref "KEY19") (pin "1") (pinfunction "1_1") (pintype "unspecified"))
      (node (ref "R34") (pin "2") (pinfunction "2_2") (pintype "unspecified"))
    )
    (net (code "22") (name "Net-(KEY20-Pad1)") (class "Default")
      (node (ref "KEY20") (pin "1") (pinfunction "1_1") (pintype "unspecified"))
      (node (ref "R40") (pin "2") (pinfunction "2_2") (pintype "unspecified"))
    )
    (net (code "23") (name "Net-(KEY21-Pad1)") (class "Default")
      (node (ref "KEY21") (pin "1") (pinfunction "1_1") (pintype "unspecified"))
      (node (ref "R39") (pin "2") (pinfunction "2_2") (pintype "unspecified"))
    )
    (net (code "24") (name "Net-(KEY22-Pad1)") (class "Default")
      (node (ref "KEY22") (pin "1") (pinfunction "1_1") (pintype "unspecified"))
      (node (ref "R38") (pin "2") (pinfunction "2_2") (pintype "unspecified"))
    )
    (net (code "25") (name "Net-(KEY23-Pad1)") (class "Default")
      (node (ref "KEY23") (pin "1") (pinfunction "1_1") (pintype "unspecified"))
      (node (ref "R37") (pin "2") (pinfunction "2_2") (pintype "unspecified"))
    )
    (net (code "26") (name "Net-(KEY24-Pad1)") (class "Default")
      (node (ref "KEY24") (pin "1") (pinfunction "1_1") (pintype "unspecified"))
      (node (ref "R36") (pin "2") (pinfunction "2_2") (pintype "unspecified"))
    )
    (net (code "27") (name "Net-(KEY25-Pad1)") (class "Default")
      (node (ref "KEY25") (pin "1") (pinfunction "1_1") (pintype "unspecified"))
      (node (ref "R41") (pin "1") (pinfunction "1_1") (pintype "unspecified"))
    )
    (net (code "28") (name "Net-(KEY26-Pad1)") (class "Default")
      (node (ref "KEY26") (pin "1") (pinfunction "1_1") (pintype "unspecified"))
      (node (ref "R42") (pin "1") (pinfunction "1_1") (pintype "unspecified"))
      (node (ref "R44") (pin "1") (pinfunction "1_1") (pintype "unspecified"))
    )
    (net (code "29") (name "Net-(KEY28-Pad1)") (class "Default")
      (node (ref "KEY28") (pin "1") (pinfunction "1_1") (pintype "unspecified"))
      (node (ref "R48") (pin "1") (pinfunction "1_1") (pintype "unspecified"))
    )
    (net (code "30") (name "Net-(KEY29-Pad1)") (class "Default")
      (node (ref "KEY29") (pin "1") (pinfunction "1_1") (pintype "unspecified"))
      (node (ref "R46") (pin "1") (pinfunction "1_1") (pintype "unspecified"))
    )
    (net (code "31") (name "Net-(KEY30-Pad1)") (class "Default")
      (node (ref "KEY30") (pin "1") (pinfunction "1_1") (pintype "unspecified"))
      (node (ref "R45") (pin "1") (pinfunction "1_1") (pintype "unspecified"))
    )
    (net (code "32") (name "Net-(KEY31-Pad1)") (class "Default")
      (node (ref "KEY31") (pin "1") (pinfunction "1_1") (pintype "unspecified"))
      (node (ref "R42") (pin "2") (pinfunction "2_2") (pintype "unspecified"))
    )
    (net (code "33") (name "Net-(KEY32-Pad1)") (class "Default")
      (node (ref "KEY32") (pin "1") (pinfunction "1_1") (pintype "unspecified"))
      (node (ref "R47") (pin "1") (pinfunction "1_1") (pintype "unspecified"))
    )
    (net (code "34") (name "Net-(KEY33-Pad1)") (class "Default")
      (node (ref "KEY33") (pin "1") (pinfunction "1_1") (pintype "unspecified"))
      (node (ref "R49") (pin "1") (pinfunction "1_1") (pintype "unspecified"))
    )
    (net (code "35") (name "Net-(KEY34-Pad1)") (class "Default")
      (node (ref "KEY34") (pin "1") (pinfunction "1_1") (pintype "unspecified"))
      (node (ref "R50") (pin "1") (pinfunction "1_1") (pintype "unspecified"))
    )
    (net (code "36") (name "Net-(KEY35-Pad1)") (class "Default")
      (node (ref "KEY35") (pin "1") (pinfunction "1_1") (pintype "unspecified"))
      (node (ref "R51") (pin "1") (pinfunction "1_1") (pintype "unspecified"))
    )
    (net (code "37") (name "Net-(KEY36-Pad1)") (class "Default")
      (node (ref "KEY36") (pin "1") (pinfunction "1_1") (pintype "unspecified"))
      (node (ref "R55") (pin "1") (pinfunction "1_1") (pintype "unspecified"))
    )
    (net (code "38") (name "Net-(KEY37-Pad1)") (class "Default")
      (node (ref "KEY37") (pin "1") (pinfunction "1_1") (pintype "unspecified"))
      (node (ref "R56") (pin "1") (pinfunction "1_1") (pintype "unspecified"))
    )
    (net (code "39") (name "Net-(KEY38-Pad1)") (class "Default")
      (node (ref "KEY38") (pin "1") (pinfunction "1_1") (pintype "unspecified"))
      (node (ref "R54") (pin "1") (pinfunction "1_1") (pintype "unspecified"))
    )
    (net (code "40") (name "Net-(KEY39-Pad1)") (class "Default")
      (node (ref "KEY39") (pin "1") (pinfunction "1_1") (pintype "unspecified"))
      (node (ref "R53") (pin "1") (pinfunction "1_1") (pintype "unspecified"))
    )
    (net (code "41") (name "Net-(KEY40-Pad1)") (class "Default")
      (node (ref "KEY40") (pin "1") (pinfunction "1_1") (pintype "unspecified"))
      (node (ref "R52") (pin "1") (pinfunction "1_1") (pintype "unspecified"))
    )
    (net (code "42") (name "Net-(KEY41-Pad1)") (class "Default")
      (node (ref "KEY41") (pin "1") (pinfunction "1_1") (pintype "unspecified"))
      (node (ref "R57") (pin "1") (pinfunction "1_1") (pintype "unspecified"))
    )
    (net (code "43") (name "Net-(KEY41-Pad2)") (class "Default")
      (node (ref "KEY41") (pin "2") (pinfunction "2_2") (pintype "unspecified"))
      (node (ref "KEY42") (pin "2") (pinfunction "2_2") (pintype "unspecified"))
      (node (ref "KEY43") (pin "2") (pinfunction "2_2") (pintype "unspecified"))
      (node (ref "KEY44") (pin "2") (pinfunction "2_2") (pintype "unspecified"))
      (node (ref "KEY45") (pin "2") (pinfunction "2_2") (pintype "unspecified"))
      (node (ref "KEY46") (pin "2") (pinfunction "2_2") (pintype "unspecified"))
      (node (ref "KEY47") (pin "2") (pinfunction "2_2") (pintype "unspecified"))
      (node (ref "KEY48") (pin "2") (pinfunction "2_2") (pintype "unspecified"))
      (node (ref "U2") (pin "99") (pinfunction "GND_99") (pintype "passive"))
    )
    (net (code "44") (name "Net-(KEY42-Pad1)") (class "Default")
      (node (ref "KEY42") (pin "1") (pinfunction "1_1") (pintype "unspecified"))
      (node (ref "R58") (pin "1") (pinfunction "1_1") (pintype "unspecified"))
    )
    (net (code "45") (name "Net-(KEY43-Pad1)") (class "Default")
      (node (ref "KEY43") (pin "1") (pinfunction "1_1") (pintype "unspecified"))
      (node (ref "R60") (pin "1") (pinfunction "1_1") (pintype "unspecified"))
    )
    (net (code "46") (name "Net-(KEY44-Pad1)") (class "Default")
      (node (ref "KEY44") (pin "1") (pinfunction "1_1") (pintype "unspecified"))
      (node (ref "R64") (pin "1") (pinfunction "1_1") (pintype "unspecified"))
    )
    (net (code "47") (name "Net-(KEY45-Pad1)") (class "Default")
      (node (ref "KEY45") (pin "1") (pinfunction "1_1") (pintype "unspecified"))
      (node (ref "R63") (pin "1") (pinfunction "1_1") (pintype "unspecified"))
    )
    (net (code "48") (name "Net-(KEY46-Pad1)") (class "Default")
      (node (ref "KEY46") (pin "1") (pinfunction "1_1") (pintype "unspecified"))
      (node (ref "R61") (pin "1") (pinfunction "1_1") (pintype "unspecified"))
    )
    (net (code "49") (name "Net-(KEY47-Pad1)") (class "Default")
      (node (ref "KEY47") (pin "1") (pinfunction "1_1") (pintype "unspecified"))
      (node (ref "R62") (pin "1") (pinfunction "1_1") (pintype "unspecified"))
    )
    (net (code "50") (name "Net-(KEY48-Pad1)") (class "Default")
      (node (ref "KEY48") (pin "1") (pinfunction "1_1") (pintype "unspecified"))
      (node (ref "R59") (pin "1") (pinfunction "1_1") (pintype "unspecified"))
    )
    (net (code "51") (name "Net-(KEY49-Pad1)") (class "Default")
      (node (ref "KEY49") (pin "1") (pinfunction "1_1") (pintype "unspecified"))
      (node (ref "R72") (pin "2") (pinfunction "2_2") (pintype "unspecified"))
    )
    (net (code "52") (name "Net-(KEY50-Pad1)") (class "Default")
      (node (ref "KEY50") (pin "1") (pinfunction "1_1") (pintype "unspecified"))
      (node (ref "R71") (pin "2") (pinfunction "2_2") (pintype "unspecified"))
    )
    (net (code "53") (name "Net-(KEY51-Pad1)") (class "Default")
      (node (ref "KEY51") (pin "1") (pinfunction "1_1") (pintype "unspecified"))
      (node (ref "R70") (pin "2") (pinfunction "2_2") (pintype "unspecified"))
    )
    (net (code "54") (name "Net-(KEY52-Pad1)") (class "Default")
      (node (ref "KEY52") (pin "1") (pinfunction "1_1") (pintype "unspecified"))
      (node (ref "R65") (pin "2") (pinfunction "2_2") (pintype "unspecified"))
    )
    (net (code "55") (name "Net-(KEY53-Pad1)") (class "Default")
      (node (ref "KEY53") (pin "1") (pinfunction "1_1") (pintype "unspecified"))
      (node (ref "R66") (pin "2") (pinfunction "2_2") (pintype "unspecified"))
    )
    (net (code "56") (name "Net-(KEY54-Pad1)") (class "Default")
      (node (ref "KEY54") (pin "1") (pinfunction "1_1") (pintype "unspecified"))
      (node (ref "R67") (pin "2") (pinfunction "2_2") (pintype "unspecified"))
    )
    (net (code "57") (name "Net-(KEY55-Pad1)") (class "Default")
      (node (ref "KEY55") (pin "1") (pinfunction "1_1") (pintype "unspecified"))
      (node (ref "R68") (pin "2") (pinfunction "2_2") (pintype "unspecified"))
    )
    (net (code "58") (name "Net-(KEY56-Pad1)") (class "Default")
      (node (ref "KEY56") (pin "1") (pinfunction "1_1") (pintype "unspecified"))
      (node (ref "R69") (pin "2") (pinfunction "2_2") (pintype "unspecified"))
    )
    (net (code "59") (name "Net-(KEY57-Pad1)") (class "Default")
      (node (ref "KEY57") (pin "1") (pinfunction "1_1") (pintype "unspecified"))
      (node (ref "R9") (pin "2") (pinfunction "2_2") (pintype "unspecified"))
    )
    (net (code "60") (name "Net-(KEY58-Pad1)") (class "Default")
      (node (ref "KEY58") (pin "1") (pinfunction "1_1") (pintype "unspecified"))
      (node (ref "R10") (pin "2") (pinfunction "2_2") (pintype "unspecified"))
    )
    (net (code "61") (name "Net-(KEY59-Pad1)") (class "Default")
      (node (ref "KEY59") (pin "1") (pinfunction "1_1") (pintype "unspecified"))
      (node (ref "R11") (pin "2") (pinfunction "2_2") (pintype "unspecified"))
    )
    (net (code "62") (name "Net-(KEY60-Pad1)") (class "Default")
      (node (ref "KEY60") (pin "1") (pinfunction "1_1") (pintype "unspecified"))
      (node (ref "R16") (pin "2") (pinfunction "2_2") (pintype "unspecified"))
    )
    (net (code "63") (name "Net-(KEY61-Pad1)") (class "Default")
      (node (ref "KEY61") (pin "1") (pinfunction "1_1") (pintype "unspecified"))
      (node (ref "R15") (pin "2") (pinfunction "2_2") (pintype "unspecified"))
    )
    (net (code "64") (name "Net-(KEY62-Pad1)") (class "Default")
      (node (ref "KEY62") (pin "1") (pinfunction "1_1") (pintype "unspecified"))
      (node (ref "R14") (pin "2") (pinfunction "2_2") (pintype "unspecified"))
    )
    (net (code "65") (name "Net-(KEY63-Pad1)") (class "Default")
      (node (ref "KEY63") (pin "1") (pinfunction "1_1") (pintype "unspecified"))
      (node (ref "R13") (pin "2") (pinfunction "2_2") (pintype "unspecified"))
      (node (ref "R21") (pin "2") (pinfunction "2_2") (pintype "unspecified"))
    )
    (net (code "66") (name "Net-(KEY64-Pad1)") (class "Default")
      (node (ref "KEY64") (pin "1") (pinfunction "1_1") (pintype "unspecified"))
      (node (ref "R12") (pin "2") (pinfunction "2_2") (pintype "unspecified"))
    )
    (net (code "67") (name "Net-(M1-Pad1)") (class "Default")
      (node (ref "M1") (pin "1") (pinfunction "1_1") (pintype "unspecified"))
      (node (ref "R1") (pin "2") (pinfunction "2_2") (pintype "unspecified"))
    )
    (net (code "68") (name "Net-(M1-Pad2)") (class "Default")
      (node (ref "M1") (pin "2") (pinfunction "2_2") (pintype "unspecified"))
      (node (ref "R2") (pin "2") (pinfunction "2_2") (pintype "unspecified"))
    )
    (net (code "69") (name "Net-(M1-Pad3)") (class "Default")
      (node (ref "M1") (pin "3") (pinfunction "3_3") (pintype "unspecified"))
      (node (ref "R3") (pin "2") (pinfunction "2_2") (pintype "unspecified"))
    )
    (net (code "70") (name "Net-(M1-Pad4)") (class "Default")
      (node (ref "M1") (pin "4") (pinfunction "4_4") (pintype "unspecified"))
      (node (ref "R4") (pin "2") (pinfunction "2_2") (pintype "unspecified"))
    )
    (net (code "71") (name "Net-(M2-Pad1)") (class "Default")
      (node (ref "M2") (pin "1") (pinfunction "1_1") (pintype "unspecified"))
      (node (ref "R5") (pin "2") (pinfunction "2_2") (pintype "unspecified"))
    )
    (net (code "72") (name "Net-(M2-Pad2)") (class "Default")
      (node (ref "M2") (pin "2") (pinfunction "2_2") (pintype "unspecified"))
      (node (ref "R6") (pin "2") (pinfunction "2_2") (pintype "unspecified"))
    )
    (net (code "73") (name "Net-(M2-Pad3)") (class "Default")
      (node (ref "M2") (pin "3") (pinfunction "3_3") (pintype "unspecified"))
      (node (ref "R7") (pin "2") (pinfunction "2_2") (pintype "unspecified"))
    )
    (net (code "74") (name "Net-(M2-Pad4)") (class "Default")
      (node (ref "M2") (pin "4") (pinfunction "4_4") (pintype "unspecified"))
      (node (ref "R8") (pin "2") (pinfunction "2_2") (pintype "unspecified"))
    )
    (net (code "75") (name "Net-(M3-+)") (class "Default")
      (node (ref "M3") (pin "2") (pinfunction "+_2") (pintype "unspecified"))
      (node (ref "U2") (pin "10") (pinfunction "VCC_10") (pintype "passive"))
    )
    (net (code "76") (name "Net-(M3--)") (class "Default")
      (node (ref "M3") (pin "3") (pinfunction "-_3") (pintype "unspecified"))
      (node (ref "U2") (pin "11") (pinfunction "GND_11") (pintype "passive"))
    )
    (net (code "77") (name "Net-(M3-PWM)") (class "Default")
      (node (ref "M3") (pin "1") (pinfunction "PWM_1") (pintype "unspecified"))
      (node (ref "U3") (pin "25") (pinfunction "PB6_(OC1BPCINT6)_25") (pintype "bidirectional"))
    )
    (net (code "78") (name "Net-(U2-PA0_(AD0))") (class "Default")
      (node (ref "R25") (pin "1") (pinfunction "1_1") (pintype "unspecified"))
      (node (ref "U2") (pin "78") (pinfunction "PA0_(AD0)_78") (pintype "bidirectional"))
    )
    (net (code "79") (name "Net-(U2-PA1_(AD1))") (class "Default")
      (node (ref "R26") (pin "1") (pinfunction "1_1") (pintype "unspecified"))
      (node (ref "U2") (pin "77") (pinfunction "PA1_(AD1)_77") (pintype "bidirectional"))
    )
    (net (code "80") (name "Net-(U2-PA2_(AD2))") (class "Default")
      (node (ref "R27") (pin "1") (pinfunction "1_1") (pintype "unspecified"))
      (node (ref "U2") (pin "76") (pinfunction "PA2_(AD2)_76") (pintype "bidirectional"))
    )
    (net (code "81") (name "Net-(U2-PA3_(AD3))") (class "Default")
      (node (ref "R28") (pin "1") (pinfunction "1_1") (pintype "unspecified"))
      (node (ref "U2") (pin "75") (pinfunction "PA3_(AD3)_75") (pintype "bidirectional"))
    )
    (net (code "82") (name "Net-(U2-PA4_(AD4))") (class "Default")
      (node (ref "R29") (pin "1") (pinfunction "1_1") (pintype "unspecified"))
      (node (ref "U2") (pin "74") (pinfunction "PA4_(AD4)_74") (pintype "bidirectional"))
    )
    (net (code "83") (name "Net-(U2-PA5_(AD5))") (class "Default")
      (node (ref "R30") (pin "1") (pinfunction "1_1") (pintype "unspecified"))
      (node (ref "U2") (pin "73") (pinfunction "PA5_(AD5)_73") (pintype "bidirectional"))
    )
    (net (code "84") (name "Net-(U2-PA6_(AD6))") (class "Default")
      (node (ref "R31") (pin "1") (pinfunction "1_1") (pintype "unspecified"))
      (node (ref "U2") (pin "72") (pinfunction "PA6_(AD6)_72") (pintype "bidirectional"))
    )
    (net (code "85") (name "Net-(U2-PA7_(AD7))") (class "Default")
      (node (ref "R32") (pin "1") (pinfunction "1_1") (pintype "unspecified"))
      (node (ref "U2") (pin "71") (pinfunction "PA7_(AD7)_71") (pintype "bidirectional"))
    )
    (net (code "86") (name "Net-(U2-PB0_(SS#PCINT0))") (class "Default")
      (node (ref "R49") (pin "2") (pinfunction "2_2") (pintype "unspecified"))
      (node (ref "U2") (pin "19") (pinfunction "PB0_(SS#PCINT0)_19") (pintype "bidirectional"))
    )
    (net (code "87") (name "Net-(U2-PB1_(SCKPCINT1))") (class "Default")
      (node (ref "R48") (pin "2") (pinfunction "2_2") (pintype "unspecified"))
      (node (ref "U2") (pin "20") (pinfunction "PB1_(SCKPCINT1)_20") (pintype "bidirectional"))
    )
    (net (code "88") (name "Net-(U2-PB2_(MOSIPCINT2))") (class "Default")
      (node (ref "R50") (pin "2") (pinfunction "2_2") (pintype "unspecified"))
      (node (ref "U2") (pin "21") (pinfunction "PB2_(MOSIPCINT2)_21") (pintype "bidirectional"))
    )
    (net (code "89") (name "Net-(U2-PB3_(MISOPCINT3))") (class "Default")
      (node (ref "R47") (pin "2") (pinfunction "2_2") (pintype "unspecified"))
      (node (ref "U2") (pin "22") (pinfunction "PB3_(MISOPCINT3)_22") (pintype "bidirectional"))
    )
    (net (code "90") (name "Net-(U2-PC0_(A8))") (class "Default")
      (node (ref "R40") (pin "1") (pinfunction "1_1") (pintype "unspecified"))
      (node (ref "U2") (pin "53") (pinfunction "PC0_(A8)_53") (pintype "bidirectional"))
    )
    (net (code "91") (name "Net-(U2-PC1_(A9))") (class "Default")
      (node (ref "R39") (pin "1") (pinfunction "1_1") (pintype "unspecified"))
      (node (ref "U2") (pin "54") (pinfunction "PC1_(A9)_54") (pintype "bidirectional"))
    )
    (net (code "92") (name "Net-(U2-PC2_(A10))") (class "Default")
      (node (ref "R38") (pin "1") (pinfunction "1_1") (pintype "unspecified"))
      (node (ref "U2") (pin "55") (pinfunction "PC2_(A10)_55") (pintype "bidirectional"))
    )
    (net (code "93") (name "Net-(U2-PC3_(A11))") (class "Default")
      (node (ref "R37") (pin "1") (pinfunction "1_1") (pintype "unspecified"))
      (node (ref "U2") (pin "56") (pinfunction "PC3_(A11)_56") (pintype "bidirectional"))
    )
    (net (code "94") (name "Net-(U2-PC4_(A12))") (class "Default")
      (node (ref "R36") (pin "1") (pinfunction "1_1") (pintype "unspecified"))
      (node (ref "U2") (pin "57") (pinfunction "PC4_(A12)_57") (pintype "bidirectional"))
    )
    (net (code "95") (name "Net-(U2-PC5_(A13))") (class "Default")
      (node (ref "R34") (pin "1") (pinfunction "1_1") (pintype "unspecified"))
      (node (ref "U2") (pin "58") (pinfunction "PC5_(A13)_58") (pintype "bidirectional"))
    )
    (net (code "96") (name "Net-(U2-PC6_(A14))") (class "Default")
      (node (ref "R35") (pin "1") (pinfunction "1_1") (pintype "unspecified"))
      (node (ref "U2") (pin "59") (pinfunction "PC6_(A14)_59") (pintype "bidirectional"))
    )
    (net (code "97") (name "Net-(U2-PC7_(A15))") (class "Default")
      (node (ref "R33") (pin "1") (pinfunction "1_1") (pintype "unspecified"))
      (node (ref "U2") (pin "60") (pinfunction "PC7_(A15)_60") (pintype "bidirectional"))
    )
    (net (code "98") (name "Net-(U2-PD7_(T0))") (class "Default")
      (node (ref "R41") (pin "2") (pinfunction "2_2") (pintype "unspecified"))
      (node (ref "U2") (pin "50") (pinfunction "PD7_(T0)_50") (pintype "bidirectional"))
    )
    (net (code "99") (name "Net-(U2-PE5_(OC3CINT5))") (class "Default")
      (node (ref "R58") (pin "2") (pinfunction "2_2") (pintype "unspecified"))
      (node (ref "U2") (pin "7") (pinfunction "PE5_(OC3CINT5)_7") (pintype "bidirectional"))
    )
    (net (code "100") (name "Net-(U2-PF2_(ADC2))") (class "Default")
      (node (ref "R9") (pin "1") (pinfunction "1_1") (pintype "unspecified"))
      (node (ref "U2") (pin "95") (pinfunction "PF2_(ADC2)_95") (pintype "bidirectional"))
    )
    (net (code "101") (name "Net-(U2-PF3_(ADC3))") (class "Default")
      (node (ref "R10") (pin "1") (pinfunction "1_1") (pintype "unspecified"))
      (node (ref "U2") (pin "94") (pinfunction "PF3_(ADC3)_94") (pintype "bidirectional"))
    )
    (net (code "102") (name "Net-(U2-PF4_(ADC4TCK))") (class "Default")
      (node (ref "R11") (pin "1") (pinfunction "1_1") (pintype "unspecified"))
      (node (ref "U2") (pin "93") (pinfunction "PF4_(ADC4TCK)_93") (pintype "bidirectional"))
    )
    (net (code "103") (name "Net-(U2-PF5_(ADC5TMS))") (class "Default")
      (node (ref "R12") (pin "1") (pinfunction "1_1") (pintype "unspecified"))
      (node (ref "U2") (pin "92") (pinfunction "PF5_(ADC5TMS)_92") (pintype "bidirectional"))
    )
    (net (code "104") (name "Net-(U2-PF6_(ADC6TDO))") (class "Default")
      (node (ref "R13") (pin "1") (pinfunction "1_1") (pintype "unspecified"))
      (node (ref "U2") (pin "91") (pinfunction "PF6_(ADC6TDO)_91") (pintype "bidirectional"))
    )
    (net (code "105") (name "Net-(U2-PF7_(ADC7TDI))") (class "Default")
      (node (ref "R14") (pin "1") (pinfunction "1_1") (pintype "unspecified"))
      (node (ref "U2") (pin "90") (pinfunction "PF7_(ADC7TDI)_90") (pintype "bidirectional"))
    )
    (net (code "106") (name "Net-(U2-PG0_(WR#))") (class "Default")
      (node (ref "R55") (pin "2") (pinfunction "2_2") (pintype "unspecified"))
      (node (ref "U2") (pin "51") (pinfunction "PG0_(WR#)_51") (pintype "bidirectional"))
    )
    (net (code "107") (name "Net-(U2-PG5_(OC0B))") (class "Default")
      (node (ref "R60") (pin "2") (pinfunction "2_2") (pintype "unspecified"))
      (node (ref "U2") (pin "1") (pinfunction "PG5_(OC0B)_1") (pintype "bidirectional"))
    )
    (net (code "108") (name "Net-(U2-PH3_(OC4A))") (class "Default")
      (node (ref "R62") (pin "2") (pinfunction "2_2") (pintype "unspecified"))
      (node (ref "U2") (pin "15") (pinfunction "PH3_(OC4A)_15") (pintype "bidirectional"))
    )
    (net (code "109") (name "Net-(U2-PH4_(OC4B))") (class "Default")
      (node (ref "R61") (pin "2") (pinfunction "2_2") (pintype "unspecified"))
      (node (ref "U2") (pin "16") (pinfunction "PH4_(OC4B)_16") (pintype "bidirectional"))
    )
    (net (code "110") (name "Net-(U2-PH5_(OC4C))") (class "Default")
      (node (ref "R63") (pin "2") (pinfunction "2_2") (pintype "unspecified"))
      (node (ref "U2") (pin "17") (pinfunction "PH5_(OC4C)_17") (pintype "bidirectional"))
    )
    (net (code "111") (name "Net-(U2-PH6_(OC2B))") (class "Default")
      (node (ref "R64") (pin "2") (pinfunction "2_2") (pintype "unspecified"))
      (node (ref "U2") (pin "18") (pinfunction "PH6_(OC2B)_18") (pintype "bidirectional"))
    )
    (net (code "112") (name "Net-(U2-PK0_(ADC8PCINT16))") (class "Default")
      (node (ref "R20") (pin "1") (pinfunction "1_1") (pintype "unspecified"))
      (node (ref "U2") (pin "89") (pinfunction "PK0_(ADC8PCINT16)_89") (pintype "bidirectional"))
    )
    (net (code "113") (name "Net-(U2-PK1_(ADC9PCINT17))") (class "Default")
      (node (ref "R21") (pin "1") (pinfunction "1_1") (pintype "unspecified"))
      (node (ref "U2") (pin "88") (pinfunction "PK1_(ADC9PCINT17)_88") (pintype "bidirectional"))
    )
    (net (code "114") (name "Net-(U2-PK2_(ADC10PCINT18))") (class "Default")
      (node (ref "R22") (pin "1") (pinfunction "1_1") (pintype "unspecified"))
      (node (ref "U2") (pin "87") (pinfunction "PK2_(ADC10PCINT18)_87") (pintype "bidirectional"))
    )
    (net (code "115") (name "Net-(U2-PK3_(ADC11PCINT19))") (class "Default")
      (node (ref "R23") (pin "1") (pinfunction "1_1") (pintype "unspecified"))
      (node (ref "U2") (pin "86") (pinfunction "PK3_(ADC11PCINT19)_86") (pintype "bidirectional"))
    )
    (net (code "116") (name "Net-(U2-PK4_(ADC12PCINT20))") (class "Default")
      (node (ref "R24") (pin "1") (pinfunction "1_1") (pintype "unspecified"))
      (node (ref "U2") (pin "85") (pinfunction "PK4_(ADC12PCINT20)_85") (pintype "bidirectional"))
    )
    (net (code "117") (name "Net-(U2-PK5_(ADC13PCINT21))") (class "Default")
      (node (ref "R15") (pin "1") (pinfunction "1_1") (pintype "unspecified"))
      (node (ref "U2") (pin "84") (pinfunction "PK5_(ADC13PCINT21)_84") (pintype "bidirectional"))
    )
    (net (code "118") (name "Net-(U2-PK6_(ADC14PCINT22))") (class "Default")
      (node (ref "R16") (pin "1") (pinfunction "1_1") (pintype "unspecified"))
      (node (ref "U2") (pin "83") (pinfunction "PK6_(ADC14PCINT22)_83") (pintype "bidirectional"))
    )
    (net (code "119") (name "Net-(U2-PK7_(ADC15PCINT23))") (class "Default")
      (node (ref "R17") (pin "1") (pinfunction "1_1") (pintype "unspecified"))
      (node (ref "U2") (pin "82") (pinfunction "PK7_(ADC15PCINT23)_82") (pintype "bidirectional"))
    )
    (net (code "120") (name "Net-(U2-PL0_(ICP4))") (class "Default")
      (node (ref "R51") (pin "2") (pinfunction "2_2") (pintype "unspecified"))
      (node (ref "U2") (pin "35") (pinfunction "PL0_(ICP4)_35") (pintype "bidirectional"))
    )
    (net (code "121") (name "Net-(U2-PL1_(ICP5))") (class "Default")
      (node (ref "R46") (pin "2") (pinfunction "2_2") (pintype "unspecified"))
      (node (ref "U2") (pin "36") (pinfunction "PL1_(ICP5)_36") (pintype "bidirectional"))
    )
    (net (code "122") (name "Net-(U2-PL2_(T5))") (class "Default")
      (node (ref "R52") (pin "2") (pinfunction "2_2") (pintype "unspecified"))
      (node (ref "U2") (pin "37") (pinfunction "PL2_(T5)_37") (pintype "bidirectional"))
    )
    (net (code "123") (name "Net-(U2-PL3_(OC5A))") (class "Default")
      (node (ref "R45") (pin "2") (pinfunction "2_2") (pintype "unspecified"))
      (node (ref "U2") (pin "38") (pinfunction "PL3_(OC5A)_38") (pintype "bidirectional"))
    )
    (net (code "124") (name "Net-(U2-PL4_(OC5B))") (class "Default")
      (node (ref "R53") (pin "2") (pinfunction "2_2") (pintype "unspecified"))
      (node (ref "U2") (pin "39") (pinfunction "PL4_(OC5B)_39") (pintype "bidirectional"))
    )
    (net (code "125") (name "Net-(U2-PL5_(OC5C))") (class "Default")
      (node (ref "R44") (pin "2") (pinfunction "2_2") (pintype "unspecified"))
      (node (ref "U2") (pin "40") (pinfunction "PL5_(OC5C)_40") (pintype "bidirectional"))
    )
    (net (code "126") (name "Net-(U2-PL6)") (class "Default")
      (node (ref "R54") (pin "2") (pinfunction "2_2") (pintype "unspecified"))
      (node (ref "U2") (pin "41") (pinfunction "PL6_41") (pintype "bidirectional"))
    )
    (net (code "127") (name "Net-(U2-PL7)") (class "Default")
      (node (ref "R43") (pin "2") (pinfunction "2_2") (pintype "unspecified"))
      (node (ref "U2") (pin "42") (pinfunction "PL7_42") (pintype "bidirectional"))
    )
    (net (code "128") (name "Net-(U3-PB4_(OC2APCINT4))") (class "Default")
      (node (ref "U3") (pin "23") (pinfunction "PB4_(OC2APCINT4)_23") (pintype "bidirectional"))
      (node (ref "U6") (pin "3") (pinfunction "3B_3") (pintype "unspecified"))
    )
    (net (code "129") (name "Net-(U3-PB5_(OC1APCINT5))") (class "Default")
      (node (ref "U3") (pin "24") (pinfunction "PB5_(OC1APCINT5)_24") (pintype "bidirectional"))
      (node (ref "U6") (pin "4") (pinfunction "4B_4") (pintype "unspecified"))
    )
    (net (code "130") (name "Net-(U3-PE3_(OC3AAIN1))") (class "Default")
      (node (ref "U3") (pin "5") (pinfunction "PE3_(OC3AAIN1)_5") (pintype "bidirectional"))
      (node (ref "U5") (pin "2") (pinfunction "2B_2") (pintype "unspecified"))
    )
    (net (code "131") (name "Net-(U3-PG5_(OC0B))") (class "Default")
      (node (ref "U3") (pin "1") (pinfunction "PG5_(OC0B)_1") (pintype "bidirectional"))
      (node (ref "U5") (pin "1") (pinfunction "1B_1") (pintype "unspecified"))
    )
    (net (code "132") (name "Net-(U3-PH3_(OC4A))") (class "Default")
      (node (ref "U3") (pin "15") (pinfunction "PH3_(OC4A)_15") (pintype "bidirectional"))
      (node (ref "U5") (pin "3") (pinfunction "3B_3") (pintype "unspecified"))
    )
    (net (code "133") (name "Net-(U3-PH4_(OC4B))") (class "Default")
      (node (ref "U3") (pin "16") (pinfunction "PH4_(OC4B)_16") (pintype "bidirectional"))
      (node (ref "U5") (pin "4") (pinfunction "4B_4") (pintype "unspecified"))
    )
    (net (code "134") (name "Net-(U3-PH5_(OC4C))") (class "Default")
      (node (ref "U3") (pin "17") (pinfunction "PH5_(OC4C)_17") (pintype "bidirectional"))
      (node (ref "U6") (pin "1") (pinfunction "1B_1") (pintype "unspecified"))
    )
    (net (code "135") (name "Net-(U3-PH6_(OC2B))") (class "Default")
      (node (ref "U3") (pin "18") (pinfunction "PH6_(OC2B)_18") (pintype "bidirectional"))
      (node (ref "U6") (pin "2") (pinfunction "2B_2") (pintype "unspecified"))
    )
    (net (code "136") (name "Net-(U3-PK0_(ADC8PCINT16))") (class "Default")
      (node (ref "R65") (pin "1") (pinfunction "1_1") (pintype "unspecified"))
      (node (ref "U3") (pin "89") (pinfunction "PK0_(ADC8PCINT16)_89") (pintype "bidirectional"))
    )
    (net (code "137") (name "Net-(U3-PK1_(ADC9PCINT17))") (class "Default")
      (node (ref "R66") (pin "1") (pinfunction "1_1") (pintype "unspecified"))
      (node (ref "U3") (pin "88") (pinfunction "PK1_(ADC9PCINT17)_88") (pintype "bidirectional"))
    )
    (net (code "138") (name "Net-(U3-PK2_(ADC10PCINT18))") (class "Default")
      (node (ref "R67") (pin "1") (pinfunction "1_1") (pintype "unspecified"))
      (node (ref "U3") (pin "87") (pinfunction "PK2_(ADC10PCINT18)_87") (pintype "bidirectional"))
    )
    (net (code "139") (name "Net-(U3-PK3_(ADC11PCINT19))") (class "Default")
      (node (ref "R68") (pin "1") (pinfunction "1_1") (pintype "unspecified"))
      (node (ref "U3") (pin "86") (pinfunction "PK3_(ADC11PCINT19)_86") (pintype "bidirectional"))
    )
    (net (code "140") (name "Net-(U3-PK4_(ADC12PCINT20))") (class "Default")
      (node (ref "R69") (pin "1") (pinfunction "1_1") (pintype "unspecified"))
      (node (ref "U3") (pin "85") (pinfunction "PK4_(ADC12PCINT20)_85") (pintype "bidirectional"))
    )
    (net (code "141") (name "Net-(U3-PK5_(ADC13PCINT21))") (class "Default")
      (node (ref "R70") (pin "1") (pinfunction "1_1") (pintype "unspecified"))
      (node (ref "U3") (pin "84") (pinfunction "PK5_(ADC13PCINT21)_84") (pintype "bidirectional"))
    )
    (net (code "142") (name "Net-(U3-PK6_(ADC14PCINT22))") (class "Default")
      (node (ref "R71") (pin "1") (pinfunction "1_1") (pintype "unspecified"))
      (node (ref "U3") (pin "83") (pinfunction "PK6_(ADC14PCINT22)_83") (pintype "bidirectional"))
    )
    (net (code "143") (name "Net-(U3-PK7_(ADC15PCINT23))") (class "Default")
      (node (ref "R72") (pin "1") (pinfunction "1_1") (pintype "unspecified"))
      (node (ref "U3") (pin "82") (pinfunction "PK7_(ADC15PCINT23)_82") (pintype "bidirectional"))
    )
    (net (code "144") (name "Net-(U5-1C)") (class "Default")
      (node (ref "R1") (pin "1") (pinfunction "1_1") (pintype "unspecified"))
      (node (ref "U5") (pin "16") (pinfunction "1C_16") (pintype "unspecified"))
    )
    (net (code "145") (name "Net-(U5-2C)") (class "Default")
      (node (ref "R2") (pin "1") (pinfunction "1_1") (pintype "unspecified"))
      (node (ref "U5") (pin "15") (pinfunction "2C_15") (pintype "unspecified"))
    )
    (net (code "146") (name "Net-(U5-3C)") (class "Default")
      (node (ref "R3") (pin "1") (pinfunction "1_1") (pintype "unspecified"))
      (node (ref "U5") (pin "14") (pinfunction "3C_14") (pintype "unspecified"))
    )
    (net (code "147") (name "Net-(U5-4C)") (class "Default")
      (node (ref "R4") (pin "1") (pinfunction "1_1") (pintype "unspecified"))
      (node (ref "U5") (pin "13") (pinfunction "4C_13") (pintype "unspecified"))
    )
    (net (code "148") (name "Net-(U5-E)") (class "Default")
      (node (ref "U2") (pin "32") (pinfunction "GND_32") (pintype "passive"))
      (node (ref "U5") (pin "8") (pinfunction "E_8") (pintype "unspecified"))
      (node (ref "U6") (pin "8") (pinfunction "E_8") (pintype "unspecified"))
    )
    (net (code "149") (name "Net-(U6-1C)") (class "Default")
      (node (ref "R5") (pin "1") (pinfunction "1_1") (pintype "unspecified"))
      (node (ref "U6") (pin "16") (pinfunction "1C_16") (pintype "unspecified"))
    )
    (net (code "150") (name "Net-(U6-2C)") (class "Default")
      (node (ref "R6") (pin "1") (pinfunction "1_1") (pintype "unspecified"))
      (node (ref "U6") (pin "15") (pinfunction "2C_15") (pintype "unspecified"))
    )
    (net (code "151") (name "Net-(U6-3C)") (class "Default")
      (node (ref "R7") (pin "1") (pinfunction "1_1") (pintype "unspecified"))
      (node (ref "U6") (pin "14") (pinfunction "3C_14") (pintype "unspecified"))
    )
    (net (code "152") (name "Net-(U6-4C)") (class "Default")
      (node (ref "R8") (pin "1") (pinfunction "1_1") (pintype "unspecified"))
      (node (ref "U6") (pin "13") (pinfunction "4C_13") (pintype "unspecified"))
    )
    (net (code "153") (name "unconnected-(KEY27-Pad1)") (class "Default")
      (node (ref "KEY27") (pin "1") (pinfunction "1_1") (pintype "unspecified"))
    )
    (net (code "154") (name "unconnected-(R18-Pad1)") (class "Default")
      (node (ref "R18") (pin "1") (pinfunction "1_1") (pintype "unspecified"))
    )
    (net (code "155") (name "unconnected-(R19-Pad1)") (class "Default")
      (node (ref "R19") (pin "1") (pinfunction "1_1") (pintype "unspecified"))
    )
    (net (code "156") (name "unconnected-(R43-Pad1)") (class "Default")
      (node (ref "R43") (pin "1") (pinfunction "1_1") (pintype "unspecified"))
    )
    (net (code "157") (name "unconnected-(R56-Pad2)") (class "Default")
      (node (ref "R56") (pin "2") (pinfunction "2_2") (pintype "unspecified"))
    )
    (net (code "158") (name "unconnected-(R57-Pad2)") (class "Default")
      (node (ref "R57") (pin "2") (pinfunction "2_2") (pintype "unspecified"))
    )
    (net (code "159") (name "unconnected-(R59-Pad2)") (class "Default")
      (node (ref "R59") (pin "2") (pinfunction "2_2") (pintype "unspecified"))
    )
    (net (code "160") (name "unconnected-(U2-AREF-Pad98)") (class "Default")
      (node (ref "U2") (pin "98") (pinfunction "AREF_98") (pintype "passive"))
    )
    (net (code "161") (name "unconnected-(U2-AVCC-Pad100)") (class "Default")
      (node (ref "U2") (pin "100") (pinfunction "AVCC_100") (pintype "passive"))
    )
    (net (code "162") (name "unconnected-(U2-PB4_(OC2APCINT4)-Pad23)") (class "Default")
      (node (ref "U2") (pin "23") (pinfunction "PB4_(OC2APCINT4)_23") (pintype "bidirectional"))
    )
    (net (code "163") (name "unconnected-(U2-PB5_(OC1APCINT5)-Pad24)") (class "Default")
      (node (ref "U2") (pin "24") (pinfunction "PB5_(OC1APCINT5)_24") (pintype "bidirectional"))
    )
    (net (code "164") (name "unconnected-(U2-PB6_(OC1BPCINT6)-Pad25)") (class "Default")
      (node (ref "U2") (pin "25") (pinfunction "PB6_(OC1BPCINT6)_25") (pintype "bidirectional"))
    )
    (net (code "165") (name "unconnected-(U2-PB7_(OC0AOC1CPCINT7)-Pad26)") (class "Default")
      (node (ref "U2") (pin "26") (pinfunction "PB7_(OC0AOC1CPCINT7)_26") (pintype "bidirectional"))
    )
    (net (code "166") (name "unconnected-(U2-PD0_(SCLINT0)-Pad43)") (class "Default")
      (node (ref "U2") (pin "43") (pinfunction "PD0_(SCLINT0)_43") (pintype "bidirectional"))
    )
    (net (code "167") (name "unconnected-(U2-PD1_(SDAINT1)-Pad44)") (class "Default")
      (node (ref "U2") (pin "44") (pinfunction "PD1_(SDAINT1)_44") (pintype "bidirectional"))
    )
    (net (code "168") (name "unconnected-(U2-PD2_(RXD1INT2)-Pad45)") (class "Default")
      (node (ref "U2") (pin "45") (pinfunction "PD2_(RXD1INT2)_45") (pintype "bidirectional"))
    )
    (net (code "169") (name "unconnected-(U2-PD3_(TXD1INT3)-Pad46)") (class "Default")
      (node (ref "U2") (pin "46") (pinfunction "PD3_(TXD1INT3)_46") (pintype "bidirectional"))
    )
    (net (code "170") (name "unconnected-(U2-PD4_(ICP1)-Pad47)") (class "Default")
      (node (ref "U2") (pin "47") (pinfunction "PD4_(ICP1)_47") (pintype "bidirectional"))
    )
    (net (code "171") (name "unconnected-(U2-PD5_(XCK1)-Pad48)") (class "Default")
      (node (ref "U2") (pin "48") (pinfunction "PD5_(XCK1)_48") (pintype "bidirectional"))
    )
    (net (code "172") (name "unconnected-(U2-PD6_(T1)-Pad49)") (class "Default")
      (node (ref "U2") (pin "49") (pinfunction "PD6_(T1)_49") (pintype "bidirectional"))
    )
    (net (code "173") (name "unconnected-(U2-PE0_(RXD0PCINT8)-Pad2)") (class "Default")
      (node (ref "U2") (pin "2") (pinfunction "PE0_(RXD0PCINT8)_2") (pintype "bidirectional"))
    )
    (net (code "174") (name "unconnected-(U2-PE1_(TXD0)-Pad3)") (class "Default")
      (node (ref "U2") (pin "3") (pinfunction "PE1_(TXD0)_3") (pintype "bidirectional"))
    )
    (net (code "175") (name "unconnected-(U2-PE2_(XCK0AIN0)-Pad4)") (class "Default")
      (node (ref "U2") (pin "4") (pinfunction "PE2_(XCK0AIN0)_4") (pintype "bidirectional"))
    )
    (net (code "176") (name "unconnected-(U2-PE3_(OC3AAIN1)-Pad5)") (class "Default")
      (node (ref "U2") (pin "5") (pinfunction "PE3_(OC3AAIN1)_5") (pintype "bidirectional"))
    )
    (net (code "177") (name "unconnected-(U2-PE4_(OC3BINT4)-Pad6)") (class "Default")
      (node (ref "U2") (pin "6") (pinfunction "PE4_(OC3BINT4)_6") (pintype "bidirectional"))
    )
    (net (code "178") (name "unconnected-(U2-PE6_(T3INT6)-Pad8)") (class "Default")
      (node (ref "U2") (pin "8") (pinfunction "PE6_(T3INT6)_8") (pintype "bidirectional"))
    )
    (net (code "179") (name "unconnected-(U2-PE7_(CLKOICP3INT7)-Pad9)") (class "Default")
      (node (ref "U2") (pin "9") (pinfunction "PE7_(CLKOICP3INT7)_9") (pintype "bidirectional"))
    )
    (net (code "180") (name "unconnected-(U2-PF0_(ADC0)-Pad97)") (class "Default")
      (node (ref "U2") (pin "97") (pinfunction "PF0_(ADC0)_97") (pintype "bidirectional"))
    )
    (net (code "181") (name "unconnected-(U2-PF1_(ADC1)-Pad96)") (class "Default")
      (node (ref "U2") (pin "96") (pinfunction "PF1_(ADC1)_96") (pintype "bidirectional"))
    )
    (net (code "182") (name "unconnected-(U2-PG1_(RD#)-Pad52)") (class "Default")
      (node (ref "U2") (pin "52") (pinfunction "PG1_(RD#)_52") (pintype "bidirectional"))
    )
    (net (code "183") (name "unconnected-(U2-PG2_(ALE)-Pad70)") (class "Default")
      (node (ref "U2") (pin "70") (pinfunction "PG2_(ALE)_70") (pintype "bidirectional"))
    )
    (net (code "184") (name "unconnected-(U2-PG3_(TOSC2)-Pad28)") (class "Default")
      (node (ref "U2") (pin "28") (pinfunction "PG3_(TOSC2)_28") (pintype "bidirectional"))
    )
    (net (code "185") (name "unconnected-(U2-PG4_(TOSC1)-Pad29)") (class "Default")
      (node (ref "U2") (pin "29") (pinfunction "PG4_(TOSC1)_29") (pintype "bidirectional"))
    )
    (net (code "186") (name "unconnected-(U2-PH0_(RXD2)-Pad12)") (class "Default")
      (node (ref "U2") (pin "12") (pinfunction "PH0_(RXD2)_12") (pintype "bidirectional"))
    )
    (net (code "187") (name "unconnected-(U2-PH1_(TXD2)-Pad13)") (class "Default")
      (node (ref "U2") (pin "13") (pinfunction "PH1_(TXD2)_13") (pintype "bidirectional"))
    )
    (net (code "188") (name "unconnected-(U2-PH2_(XCK2)-Pad14)") (class "Default")
      (node (ref "U2") (pin "14") (pinfunction "PH2_(XCK2)_14") (pintype "bidirectional"))
    )
    (net (code "189") (name "unconnected-(U2-PH7_(T4)-Pad27)") (class "Default")
      (node (ref "U2") (pin "27") (pinfunction "PH7_(T4)_27") (pintype "bidirectional"))
    )
    (net (code "190") (name "unconnected-(U2-PJ0_(RXD3PCINT9)-Pad63)") (class "Default")
      (node (ref "U2") (pin "63") (pinfunction "PJ0_(RXD3PCINT9)_63") (pintype "bidirectional"))
    )
    (net (code "191") (name "unconnected-(U2-PJ1_(TXD3PCINT10)-Pad64)") (class "Default")
      (node (ref "U2") (pin "64") (pinfunction "PJ1_(TXD3PCINT10)_64") (pintype "bidirectional"))
    )
    (net (code "192") (name "unconnected-(U2-PJ2_(XCK3PCINT11)-Pad65)") (class "Default")
      (node (ref "U2") (pin "65") (pinfunction "PJ2_(XCK3PCINT11)_65") (pintype "bidirectional"))
    )
    (net (code "193") (name "unconnected-(U2-PJ3_(PCINT12)-Pad66)") (class "Default")
      (node (ref "U2") (pin "66") (pinfunction "PJ3_(PCINT12)_66") (pintype "bidirectional"))
    )
    (net (code "194") (name "unconnected-(U2-PJ4_(PCINT13)-Pad67)") (class "Default")
      (node (ref "U2") (pin "67") (pinfunction "PJ4_(PCINT13)_67") (pintype "bidirectional"))
    )
    (net (code "195") (name "unconnected-(U2-PJ5_(PCINT14)-Pad68)") (class "Default")
      (node (ref "U2") (pin "68") (pinfunction "PJ5_(PCINT14)_68") (pintype "bidirectional"))
    )
    (net (code "196") (name "unconnected-(U2-PJ6_(PCINT15)-Pad69)") (class "Default")
      (node (ref "U2") (pin "69") (pinfunction "PJ6_(PCINT15)_69") (pintype "bidirectional"))
    )
    (net (code "197") (name "unconnected-(U2-PJ7-Pad79)") (class "Default")
      (node (ref "U2") (pin "79") (pinfunction "PJ7_79") (pintype "bidirectional"))
    )
    (net (code "198") (name "unconnected-(U2-RESET#-Pad30)") (class "Default")
      (node (ref "U2") (pin "30") (pinfunction "RESET#_30") (pintype "unspecified"))
    )
    (net (code "199") (name "unconnected-(U2-VCC-Pad31)") (class "Default")
      (node (ref "U2") (pin "31") (pinfunction "VCC_31") (pintype "passive"))
    )
    (net (code "200") (name "unconnected-(U2-VCC-Pad61)") (class "Default")
      (node (ref "U2") (pin "61") (pinfunction "VCC_61") (pintype "passive"))
    )
    (net (code "201") (name "unconnected-(U2-VCC-Pad80)") (class "Default")
      (node (ref "U2") (pin "80") (pinfunction "VCC_80") (pintype "passive"))
    )
    (net (code "202") (name "unconnected-(U2-XTAL1-Pad34)") (class "Default")
      (node (ref "U2") (pin "34") (pinfunction "XTAL1_34") (pintype "unspecified"))
    )
    (net (code "203") (name "unconnected-(U2-XTAL2-Pad33)") (class "Default")
      (node (ref "U2") (pin "33") (pinfunction "XTAL2_33") (pintype "output"))
    )
    (net (code "204") (name "unconnected-(U3-AREF-Pad98)") (class "Default")
      (node (ref "U3") (pin "98") (pinfunction "AREF_98") (pintype "passive"))
    )
    (net (code "205") (name "unconnected-(U3-AVCC-Pad100)") (class "Default")
      (node (ref "U3") (pin "100") (pinfunction "AVCC_100") (pintype "passive"))
    )
    (net (code "206") (name "unconnected-(U3-GND-Pad11)") (class "Default")
      (node (ref "U3") (pin "11") (pinfunction "GND_11") (pintype "passive"))
    )
    (net (code "207") (name "unconnected-(U3-GND-Pad32)") (class "Default")
      (node (ref "U3") (pin "32") (pinfunction "GND_32") (pintype "passive"))
    )
    (net (code "208") (name "unconnected-(U3-GND-Pad62)") (class "Default")
      (node (ref "U3") (pin "62") (pinfunction "GND_62") (pintype "passive"))
    )
    (net (code "209") (name "unconnected-(U3-GND-Pad81)") (class "Default")
      (node (ref "U3") (pin "81") (pinfunction "GND_81") (pintype "passive"))
    )
    (net (code "210") (name "unconnected-(U3-GND-Pad99)") (class "Default")
      (node (ref "U3") (pin "99") (pinfunction "GND_99") (pintype "passive"))
    )
    (net (code "211") (name "unconnected-(U3-PA0_(AD0)-Pad78)") (class "Default")
      (node (ref "U3") (pin "78") (pinfunction "PA0_(AD0)_78") (pintype "bidirectional"))
    )
    (net (code "212") (name "unconnected-(U3-PA1_(AD1)-Pad77)") (class "Default")
      (node (ref "U3") (pin "77") (pinfunction "PA1_(AD1)_77") (pintype "bidirectional"))
    )
    (net (code "213") (name "unconnected-(U3-PA2_(AD2)-Pad76)") (class "Default")
      (node (ref "U3") (pin "76") (pinfunction "PA2_(AD2)_76") (pintype "bidirectional"))
    )
    (net (code "214") (name "unconnected-(U3-PA3_(AD3)-Pad75)") (class "Default")
      (node (ref "U3") (pin "75") (pinfunction "PA3_(AD3)_75") (pintype "bidirectional"))
    )
    (net (code "215") (name "unconnected-(U3-PA4_(AD4)-Pad74)") (class "Default")
      (node (ref "U3") (pin "74") (pinfunction "PA4_(AD4)_74") (pintype "bidirectional"))
    )
    (net (code "216") (name "unconnected-(U3-PA5_(AD5)-Pad73)") (class "Default")
      (node (ref "U3") (pin "73") (pinfunction "PA5_(AD5)_73") (pintype "bidirectional"))
    )
    (net (code "217") (name "unconnected-(U3-PA6_(AD6)-Pad72)") (class "Default")
      (node (ref "U3") (pin "72") (pinfunction "PA6_(AD6)_72") (pintype "bidirectional"))
    )
    (net (code "218") (name "unconnected-(U3-PA7_(AD7)-Pad71)") (class "Default")
      (node (ref "U3") (pin "71") (pinfunction "PA7_(AD7)_71") (pintype "bidirectional"))
    )
    (net (code "219") (name "unconnected-(U3-PB0_(SS#PCINT0)-Pad19)") (class "Default")
      (node (ref "U3") (pin "19") (pinfunction "PB0_(SS#PCINT0)_19") (pintype "bidirectional"))
    )
    (net (code "220") (name "unconnected-(U3-PB1_(SCKPCINT1)-Pad20)") (class "Default")
      (node (ref "U3") (pin "20") (pinfunction "PB1_(SCKPCINT1)_20") (pintype "bidirectional"))
    )
    (net (code "221") (name "unconnected-(U3-PB2_(MOSIPCINT2)-Pad21)") (class "Default")
      (node (ref "U3") (pin "21") (pinfunction "PB2_(MOSIPCINT2)_21") (pintype "bidirectional"))
    )
    (net (code "222") (name "unconnected-(U3-PB3_(MISOPCINT3)-Pad22)") (class "Default")
      (node (ref "U3") (pin "22") (pinfunction "PB3_(MISOPCINT3)_22") (pintype "bidirectional"))
    )
    (net (code "223") (name "unconnected-(U3-PB7_(OC0AOC1CPCINT7)-Pad26)") (class "Default")
      (node (ref "U3") (pin "26") (pinfunction "PB7_(OC0AOC1CPCINT7)_26") (pintype "bidirectional"))
    )
    (net (code "224") (name "unconnected-(U3-PC0_(A8)-Pad53)") (class "Default")
      (node (ref "U3") (pin "53") (pinfunction "PC0_(A8)_53") (pintype "bidirectional"))
    )
    (net (code "225") (name "unconnected-(U3-PC1_(A9)-Pad54)") (class "Default")
      (node (ref "U3") (pin "54") (pinfunction "PC1_(A9)_54") (pintype "bidirectional"))
    )
    (net (code "226") (name "unconnected-(U3-PC2_(A10)-Pad55)") (class "Default")
      (node (ref "U3") (pin "55") (pinfunction "PC2_(A10)_55") (pintype "bidirectional"))
    )
    (net (code "227") (name "unconnected-(U3-PC3_(A11)-Pad56)") (class "Default")
      (node (ref "U3") (pin "56") (pinfunction "PC3_(A11)_56") (pintype "bidirectional"))
    )
    (net (code "228") (name "unconnected-(U3-PC4_(A12)-Pad57)") (class "Default")
      (node (ref "U3") (pin "57") (pinfunction "PC4_(A12)_57") (pintype "bidirectional"))
    )
    (net (code "229") (name "unconnected-(U3-PC5_(A13)-Pad58)") (class "Default")
      (node (ref "U3") (pin "58") (pinfunction "PC5_(A13)_58") (pintype "bidirectional"))
    )
    (net (code "230") (name "unconnected-(U3-PC6_(A14)-Pad59)") (class "Default")
      (node (ref "U3") (pin "59") (pinfunction "PC6_(A14)_59") (pintype "bidirectional"))
    )
    (net (code "231") (name "unconnected-(U3-PC7_(A15)-Pad60)") (class "Default")
      (node (ref "U3") (pin "60") (pinfunction "PC7_(A15)_60") (pintype "bidirectional"))
    )
    (net (code "232") (name "unconnected-(U3-PD0_(SCLINT0)-Pad43)") (class "Default")
      (node (ref "U3") (pin "43") (pinfunction "PD0_(SCLINT0)_43") (pintype "bidirectional"))
    )
    (net (code "233") (name "unconnected-(U3-PD1_(SDAINT1)-Pad44)") (class "Default")
      (node (ref "U3") (pin "44") (pinfunction "PD1_(SDAINT1)_44") (pintype "bidirectional"))
    )
    (net (code "234") (name "unconnected-(U3-PD2_(RXD1INT2)-Pad45)") (class "Default")
      (node (ref "U3") (pin "45") (pinfunction "PD2_(RXD1INT2)_45") (pintype "bidirectional"))
    )
    (net (code "235") (name "unconnected-(U3-PD3_(TXD1INT3)-Pad46)") (class "Default")
      (node (ref "U3") (pin "46") (pinfunction "PD3_(TXD1INT3)_46") (pintype "bidirectional"))
    )
    (net (code "236") (name "unconnected-(U3-PD4_(ICP1)-Pad47)") (class "Default")
      (node (ref "U3") (pin "47") (pinfunction "PD4_(ICP1)_47") (pintype "bidirectional"))
    )
    (net (code "237") (name "unconnected-(U3-PD5_(XCK1)-Pad48)") (class "Default")
      (node (ref "U3") (pin "48") (pinfunction "PD5_(XCK1)_48") (pintype "bidirectional"))
    )
    (net (code "238") (name "unconnected-(U3-PD6_(T1)-Pad49)") (class "Default")
      (node (ref "U3") (pin "49") (pinfunction "PD6_(T1)_49") (pintype "bidirectional"))
    )
    (net (code "239") (name "unconnected-(U3-PD7_(T0)-Pad50)") (class "Default")
      (node (ref "U3") (pin "50") (pinfunction "PD7_(T0)_50") (pintype "bidirectional"))
    )
    (net (code "240") (name "unconnected-(U3-PE0_(RXD0PCINT8)-Pad2)") (class "Default")
      (node (ref "U3") (pin "2") (pinfunction "PE0_(RXD0PCINT8)_2") (pintype "bidirectional"))
    )
    (net (code "241") (name "unconnected-(U3-PE1_(TXD0)-Pad3)") (class "Default")
      (node (ref "U3") (pin "3") (pinfunction "PE1_(TXD0)_3") (pintype "bidirectional"))
    )
    (net (code "242") (name "unconnected-(U3-PE2_(XCK0AIN0)-Pad4)") (class "Default")
      (node (ref "U3") (pin "4") (pinfunction "PE2_(XCK0AIN0)_4") (pintype "bidirectional"))
    )
    (net (code "243") (name "unconnected-(U3-PE4_(OC3BINT4)-Pad6)") (class "Default")
      (node (ref "U3") (pin "6") (pinfunction "PE4_(OC3BINT4)_6") (pintype "bidirectional"))
    )
    (net (code "244") (name "unconnected-(U3-PE5_(OC3CINT5)-Pad7)") (class "Default")
      (node (ref "U3") (pin "7") (pinfunction "PE5_(OC3CINT5)_7") (pintype "bidirectional"))
    )
    (net (code "245") (name "unconnected-(U3-PE6_(T3INT6)-Pad8)") (class "Default")
      (node (ref "U3") (pin "8") (pinfunction "PE6_(T3INT6)_8") (pintype "bidirectional"))
    )
    (net (code "246") (name "unconnected-(U3-PE7_(CLKOICP3INT7)-Pad9)") (class "Default")
      (node (ref "U3") (pin "9") (pinfunction "PE7_(CLKOICP3INT7)_9") (pintype "bidirectional"))
    )
    (net (code "247") (name "unconnected-(U3-PF0_(ADC0)-Pad97)") (class "Default")
      (node (ref "U3") (pin "97") (pinfunction "PF0_(ADC0)_97") (pintype "bidirectional"))
    )
    (net (code "248") (name "unconnected-(U3-PF1_(ADC1)-Pad96)") (class "Default")
      (node (ref "U3") (pin "96") (pinfunction "PF1_(ADC1)_96") (pintype "bidirectional"))
    )
    (net (code "249") (name "unconnected-(U3-PF2_(ADC2)-Pad95)") (class "Default")
      (node (ref "U3") (pin "95") (pinfunction "PF2_(ADC2)_95") (pintype "bidirectional"))
    )
    (net (code "250") (name "unconnected-(U3-PF3_(ADC3)-Pad94)") (class "Default")
      (node (ref "U3") (pin "94") (pinfunction "PF3_(ADC3)_94") (pintype "bidirectional"))
    )
    (net (code "251") (name "unconnected-(U3-PF4_(ADC4TCK)-Pad93)") (class "Default")
      (node (ref "U3") (pin "93") (pinfunction "PF4_(ADC4TCK)_93") (pintype "bidirectional"))
    )
    (net (code "252") (name "unconnected-(U3-PF5_(ADC5TMS)-Pad92)") (class "Default")
      (node (ref "U3") (pin "92") (pinfunction "PF5_(ADC5TMS)_92") (pintype "bidirectional"))
    )
    (net (code "253") (name "unconnected-(U3-PF6_(ADC6TDO)-Pad91)") (class "Default")
      (node (ref "U3") (pin "91") (pinfunction "PF6_(ADC6TDO)_91") (pintype "bidirectional"))
    )
    (net (code "254") (name "unconnected-(U3-PF7_(ADC7TDI)-Pad90)") (class "Default")
      (node (ref "U3") (pin "90") (pinfunction "PF7_(ADC7TDI)_90") (pintype "bidirectional"))
    )
    (net (code "255") (name "unconnected-(U3-PG0_(WR#)-Pad51)") (class "Default")
      (node (ref "U3") (pin "51") (pinfunction "PG0_(WR#)_51") (pintype "bidirectional"))
    )
    (net (code "256") (name "unconnected-(U3-PG1_(RD#)-Pad52)") (class "Default")
      (node (ref "U3") (pin "52") (pinfunction "PG1_(RD#)_52") (pintype "bidirectional"))
    )
    (net (code "257") (name "unconnected-(U3-PG2_(ALE)-Pad70)") (class "Default")
      (node (ref "U3") (pin "70") (pinfunction "PG2_(ALE)_70") (pintype "bidirectional"))
    )
    (net (code "258") (name "unconnected-(U3-PG3_(TOSC2)-Pad28)") (class "Default")
      (node (ref "U3") (pin "28") (pinfunction "PG3_(TOSC2)_28") (pintype "bidirectional"))
    )
    (net (code "259") (name "unconnected-(U3-PG4_(TOSC1)-Pad29)") (class "Default")
      (node (ref "U3") (pin "29") (pinfunction "PG4_(TOSC1)_29") (pintype "bidirectional"))
    )
    (net (code "260") (name "unconnected-(U3-PH0_(RXD2)-Pad12)") (class "Default")
      (node (ref "U3") (pin "12") (pinfunction "PH0_(RXD2)_12") (pintype "bidirectional"))
    )
    (net (code "261") (name "unconnected-(U3-PH1_(TXD2)-Pad13)") (class "Default")
      (node (ref "U3") (pin "13") (pinfunction "PH1_(TXD2)_13") (pintype "bidirectional"))
    )
    (net (code "262") (name "unconnected-(U3-PH2_(XCK2)-Pad14)") (class "Default")
      (node (ref "U3") (pin "14") (pinfunction "PH2_(XCK2)_14") (pintype "bidirectional"))
    )
    (net (code "263") (name "unconnected-(U3-PH7_(T4)-Pad27)") (class "Default")
      (node (ref "U3") (pin "27") (pinfunction "PH7_(T4)_27") (pintype "bidirectional"))
    )
    (net (code "264") (name "unconnected-(U3-PJ0_(RXD3PCINT9)-Pad63)") (class "Default")
      (node (ref "U3") (pin "63") (pinfunction "PJ0_(RXD3PCINT9)_63") (pintype "bidirectional"))
    )
    (net (code "265") (name "unconnected-(U3-PJ1_(TXD3PCINT10)-Pad64)") (class "Default")
      (node (ref "U3") (pin "64") (pinfunction "PJ1_(TXD3PCINT10)_64") (pintype "bidirectional"))
    )
    (net (code "266") (name "unconnected-(U3-PJ2_(XCK3PCINT11)-Pad65)") (class "Default")
      (node (ref "U3") (pin "65") (pinfunction "PJ2_(XCK3PCINT11)_65") (pintype "bidirectional"))
    )
    (net (code "267") (name "unconnected-(U3-PJ3_(PCINT12)-Pad66)") (class "Default")
      (node (ref "U3") (pin "66") (pinfunction "PJ3_(PCINT12)_66") (pintype "bidirectional"))
    )
    (net (code "268") (name "unconnected-(U3-PJ4_(PCINT13)-Pad67)") (class "Default")
      (node (ref "U3") (pin "67") (pinfunction "PJ4_(PCINT13)_67") (pintype "bidirectional"))
    )
    (net (code "269") (name "unconnected-(U3-PJ5_(PCINT14)-Pad68)") (class "Default")
      (node (ref "U3") (pin "68") (pinfunction "PJ5_(PCINT14)_68") (pintype "bidirectional"))
    )
    (net (code "270") (name "unconnected-(U3-PJ6_(PCINT15)-Pad69)") (class "Default")
      (node (ref "U3") (pin "69") (pinfunction "PJ6_(PCINT15)_69") (pintype "bidirectional"))
    )
    (net (code "271") (name "unconnected-(U3-PJ7-Pad79)") (class "Default")
      (node (ref "U3") (pin "79") (pinfunction "PJ7_79") (pintype "bidirectional"))
    )
    (net (code "272") (name "unconnected-(U3-PL0_(ICP4)-Pad35)") (class "Default")
      (node (ref "U3") (pin "35") (pinfunction "PL0_(ICP4)_35") (pintype "bidirectional"))
    )
    (net (code "273") (name "unconnected-(U3-PL1_(ICP5)-Pad36)") (class "Default")
      (node (ref "U3") (pin "36") (pinfunction "PL1_(ICP5)_36") (pintype "bidirectional"))
    )
    (net (code "274") (name "unconnected-(U3-PL2_(T5)-Pad37)") (class "Default")
      (node (ref "U3") (pin "37") (pinfunction "PL2_(T5)_37") (pintype "bidirectional"))
    )
    (net (code "275") (name "unconnected-(U3-PL3_(OC5A)-Pad38)") (class "Default")
      (node (ref "U3") (pin "38") (pinfunction "PL3_(OC5A)_38") (pintype "bidirectional"))
    )
    (net (code "276") (name "unconnected-(U3-PL4_(OC5B)-Pad39)") (class "Default")
      (node (ref "U3") (pin "39") (pinfunction "PL4_(OC5B)_39") (pintype "bidirectional"))
    )
    (net (code "277") (name "unconnected-(U3-PL5_(OC5C)-Pad40)") (class "Default")
      (node (ref "U3") (pin "40") (pinfunction "PL5_(OC5C)_40") (pintype "bidirectional"))
    )
    (net (code "278") (name "unconnected-(U3-PL6-Pad41)") (class "Default")
      (node (ref "U3") (pin "41") (pinfunction "PL6_41") (pintype "bidirectional"))
    )
    (net (code "279") (name "unconnected-(U3-PL7-Pad42)") (class "Default")
      (node (ref "U3") (pin "42") (pinfunction "PL7_42") (pintype "bidirectional"))
    )
    (net (code "280") (name "unconnected-(U3-RESET#-Pad30)") (class "Default")
      (node (ref "U3") (pin "30") (pinfunction "RESET#_30") (pintype "unspecified"))
    )
    (net (code "281") (name "unconnected-(U3-VCC-Pad10)") (class "Default")
      (node (ref "U3") (pin "10") (pinfunction "VCC_10") (pintype "passive"))
    )
    (net (code "282") (name "unconnected-(U3-VCC-Pad31)") (class "Default")
      (node (ref "U3") (pin "31") (pinfunction "VCC_31") (pintype "passive"))
    )
    (net (code "283") (name "unconnected-(U3-VCC-Pad61)") (class "Default")
      (node (ref "U3") (pin "61") (pinfunction "VCC_61") (pintype "passive"))
    )
    (net (code "284") (name "unconnected-(U3-VCC-Pad80)") (class "Default")
      (node (ref "U3") (pin "80") (pinfunction "VCC_80") (pintype "passive"))
    )
    (net (code "285") (name "unconnected-(U3-XTAL1-Pad34)") (class "Default")
      (node (ref "U3") (pin "34") (pinfunction "XTAL1_34") (pintype "unspecified"))
    )
    (net (code "286") (name "unconnected-(U3-XTAL2-Pad33)") (class "Default")
      (node (ref "U3") (pin "33") (pinfunction "XTAL2_33") (pintype "output"))
    )
    (net (code "287") (name "unconnected-(U5-5B-Pad5)") (class "Default")
      (node (ref "U5") (pin "5") (pinfunction "5B_5") (pintype "unspecified"))
    )
    (net (code "288") (name "unconnected-(U5-5C-Pad12)") (class "Default")
      (node (ref "U5") (pin "12") (pinfunction "5C_12") (pintype "unspecified"))
    )
    (net (code "289") (name "unconnected-(U5-6B-Pad6)") (class "Default")
      (node (ref "U5") (pin "6") (pinfunction "6B_6") (pintype "unspecified"))
    )
    (net (code "290") (name "unconnected-(U5-6C-Pad11)") (class "Default")
      (node (ref "U5") (pin "11") (pinfunction "6C_11") (pintype "unspecified"))
    )
    (net (code "291") (name "unconnected-(U5-7B-Pad7)") (class "Default")
      (node (ref "U5") (pin "7") (pinfunction "7B_7") (pintype "unspecified"))
    )
    (net (code "292") (name "unconnected-(U5-7C-Pad10)") (class "Default")
      (node (ref "U5") (pin "10") (pinfunction "7C_10") (pintype "unspecified"))
    )
    (net (code "293") (name "unconnected-(U5-COM-Pad9)") (class "Default")
      (node (ref "U5") (pin "9") (pinfunction "COM_9") (pintype "unspecified"))
    )
    (net (code "294") (name "unconnected-(U6-5B-Pad5)") (class "Default")
      (node (ref "U6") (pin "5") (pinfunction "5B_5") (pintype "unspecified"))
    )
    (net (code "295") (name "unconnected-(U6-5C-Pad12)") (class "Default")
      (node (ref "U6") (pin "12") (pinfunction "5C_12") (pintype "unspecified"))
    )
    (net (code "296") (name "unconnected-(U6-6B-Pad6)") (class "Default")
      (node (ref "U6") (pin "6") (pinfunction "6B_6") (pintype "unspecified"))
    )
    (net (code "297") (name "unconnected-(U6-6C-Pad11)") (class "Default")
      (node (ref "U6") (pin "11") (pinfunction "6C_11") (pintype "unspecified"))
    )
    (net (code "298") (name "unconnected-(U6-7B-Pad7)") (class "Default")
      (node (ref "U6") (pin "7") (pinfunction "7B_7") (pintype "unspecified"))
    )
    (net (code "299") (name "unconnected-(U6-7C-Pad10)") (class "Default")
      (node (ref "U6") (pin "10") (pinfunction "7C_10") (pintype "unspecified"))
    )
    (net (code "300") (name "unconnected-(U6-COM-Pad9)") (class "Default")
      (node (ref "U6") (pin "9") (pinfunction "COM_9") (pintype "unspecified"))
    )
  )
)
